# citizen_science_flora_v2_DFA_corrected.net
KiCad netlist of a schematic drawn in EAGLE
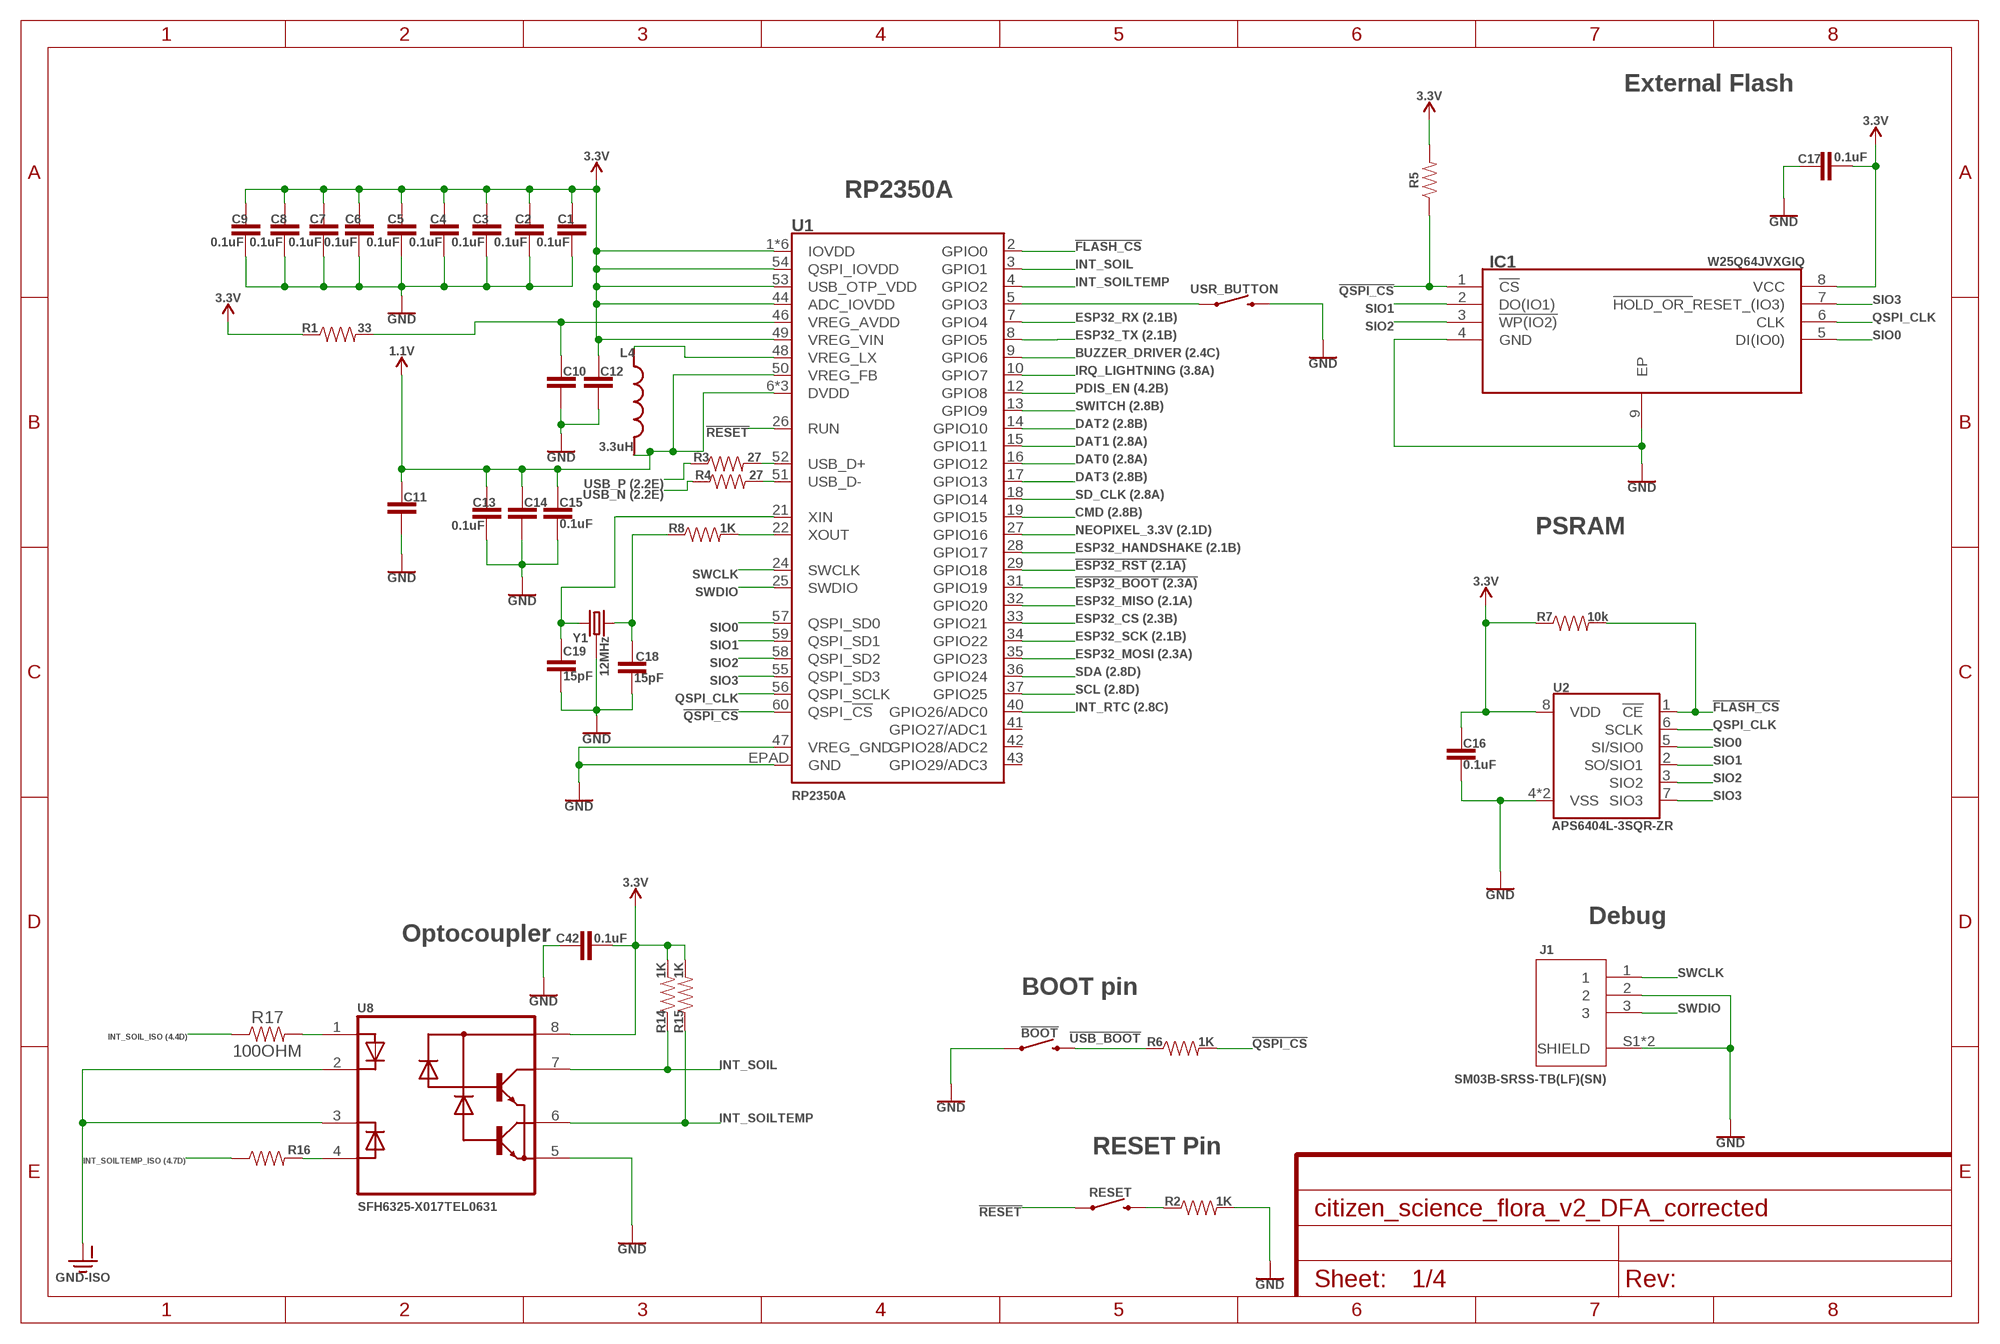
[diagram p0: schematic, sheet 1]
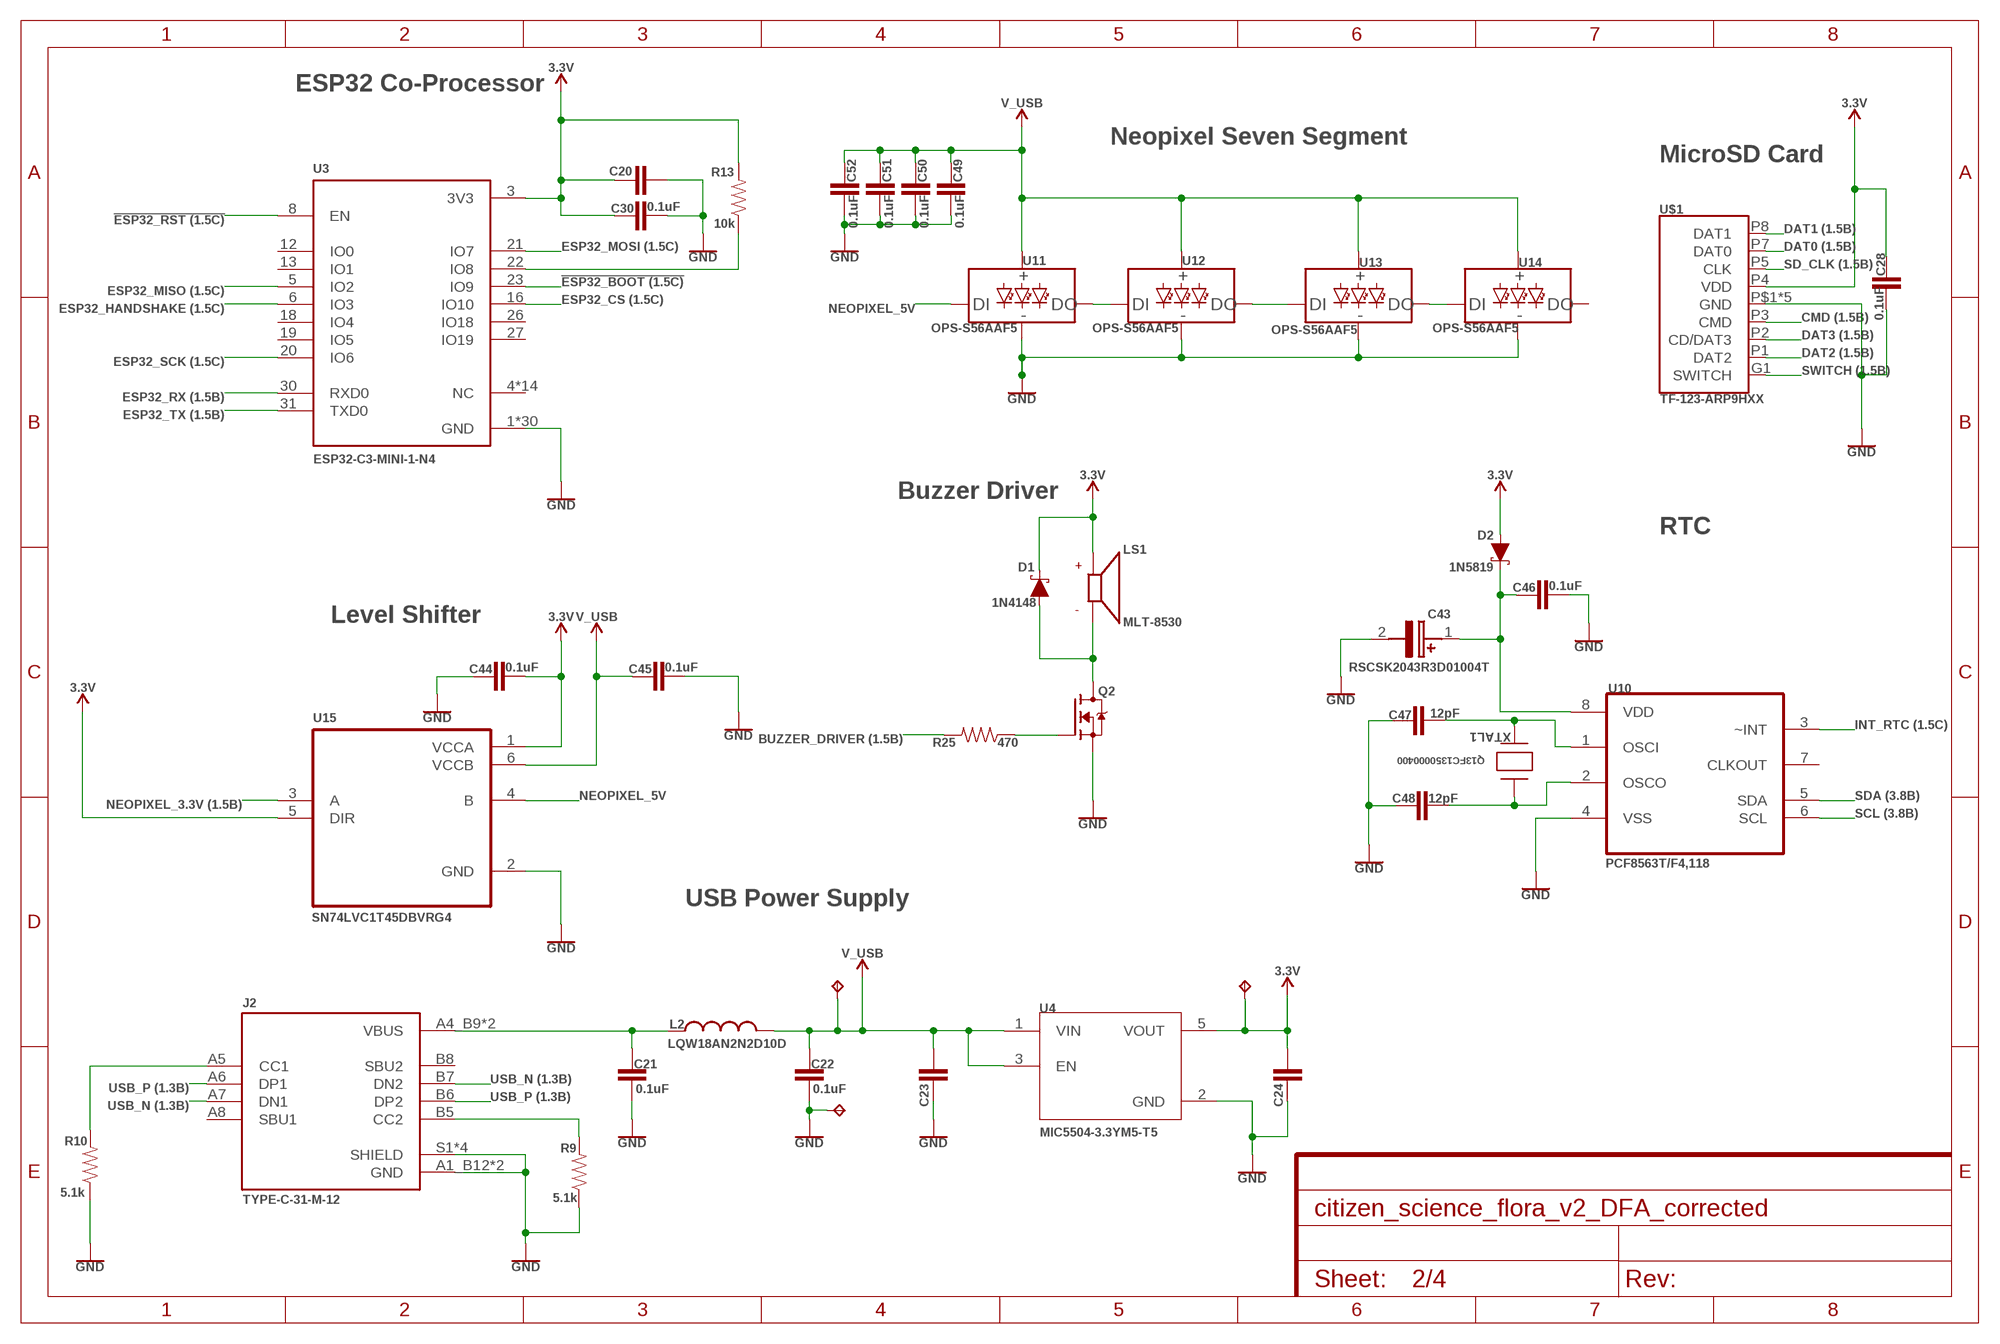
[diagram p1: schematic, sheet 2]
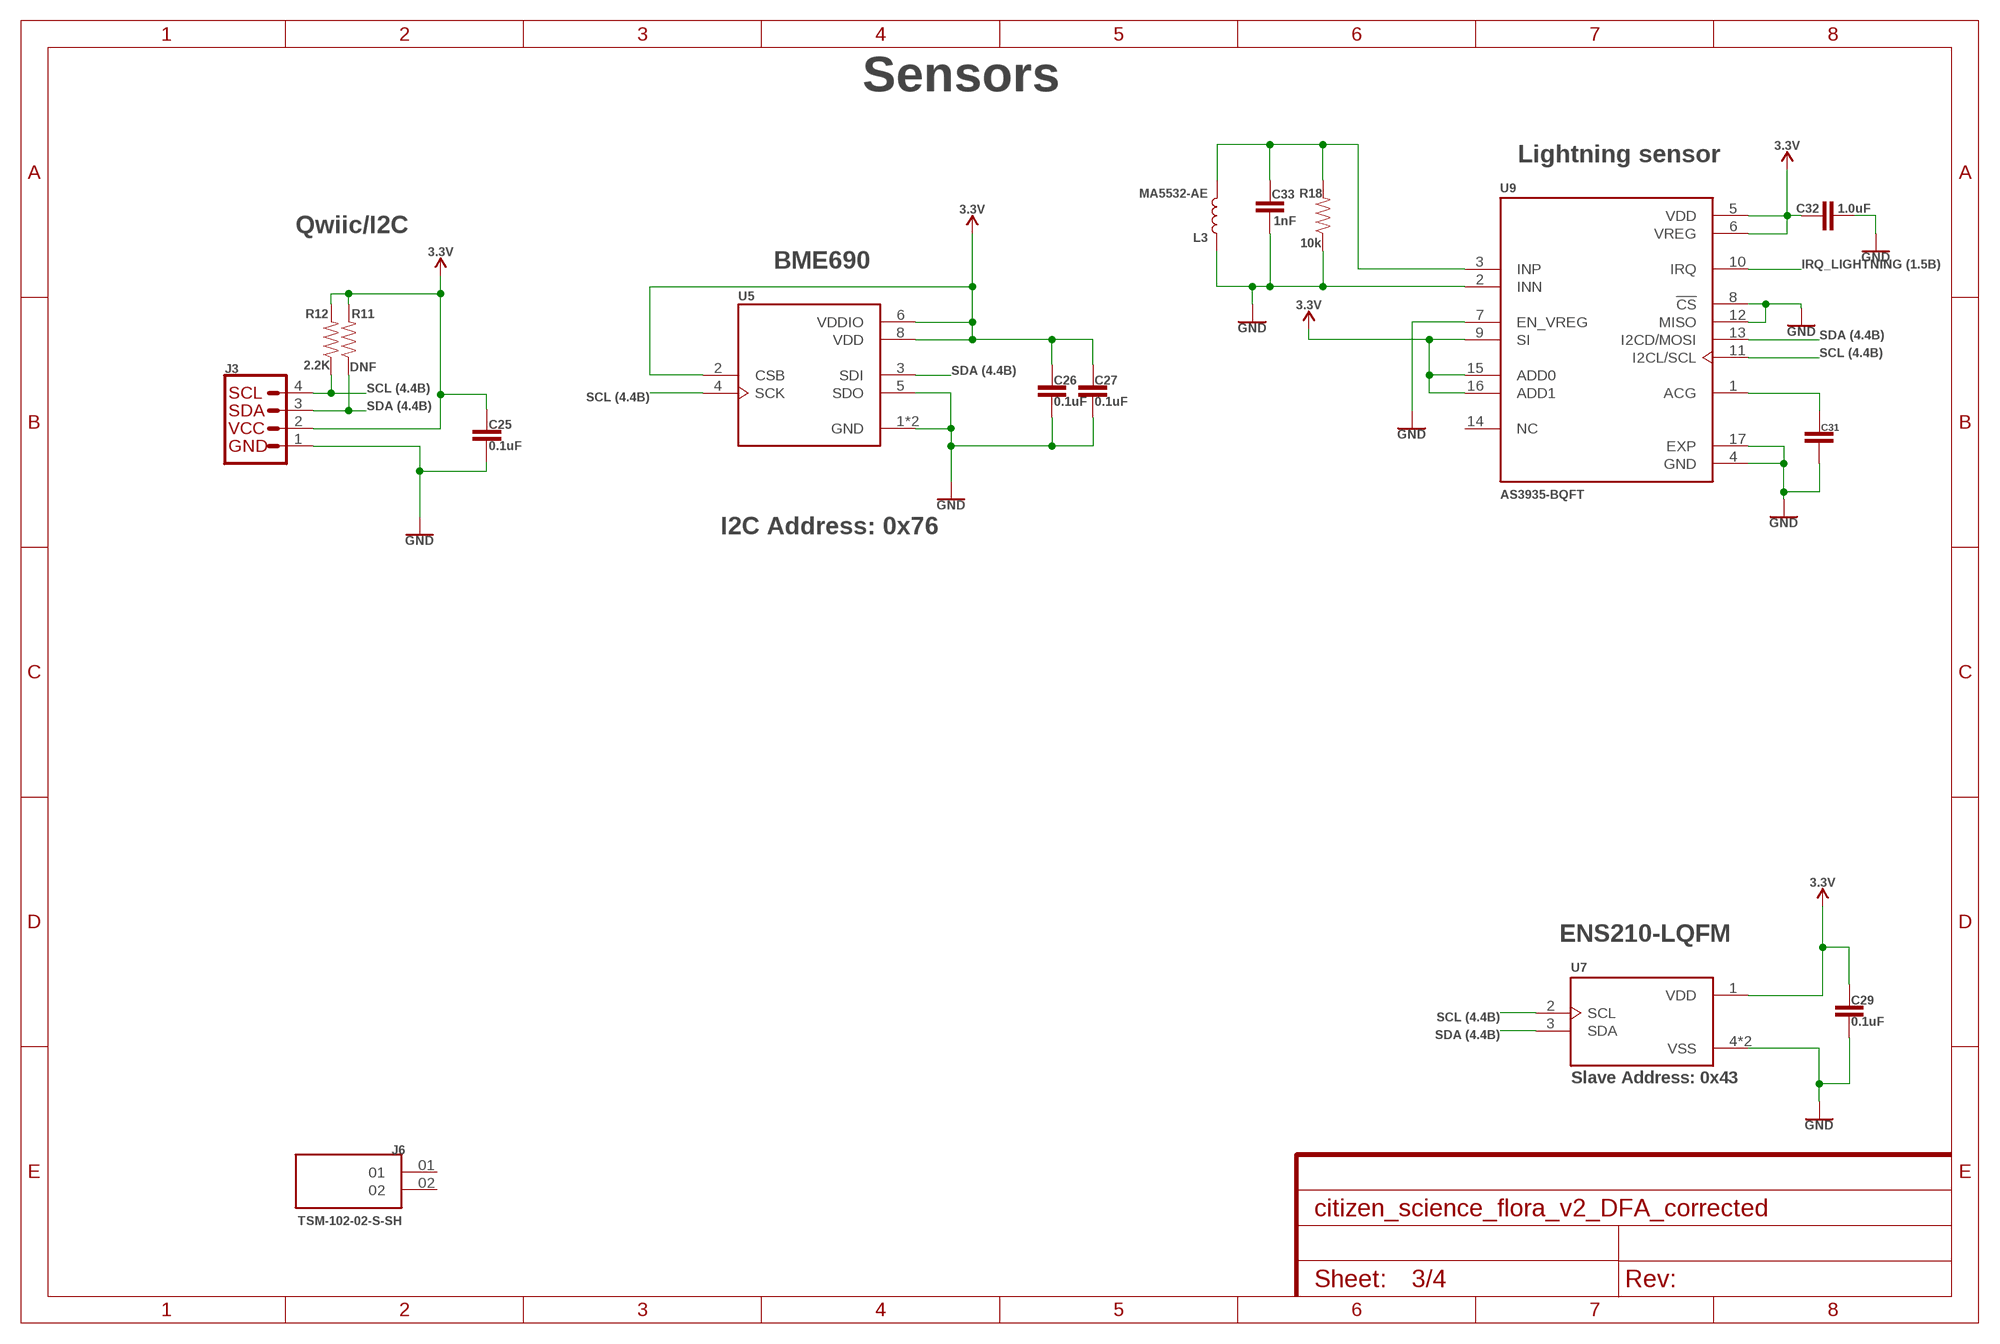
[diagram p2: schematic, sheet 3]
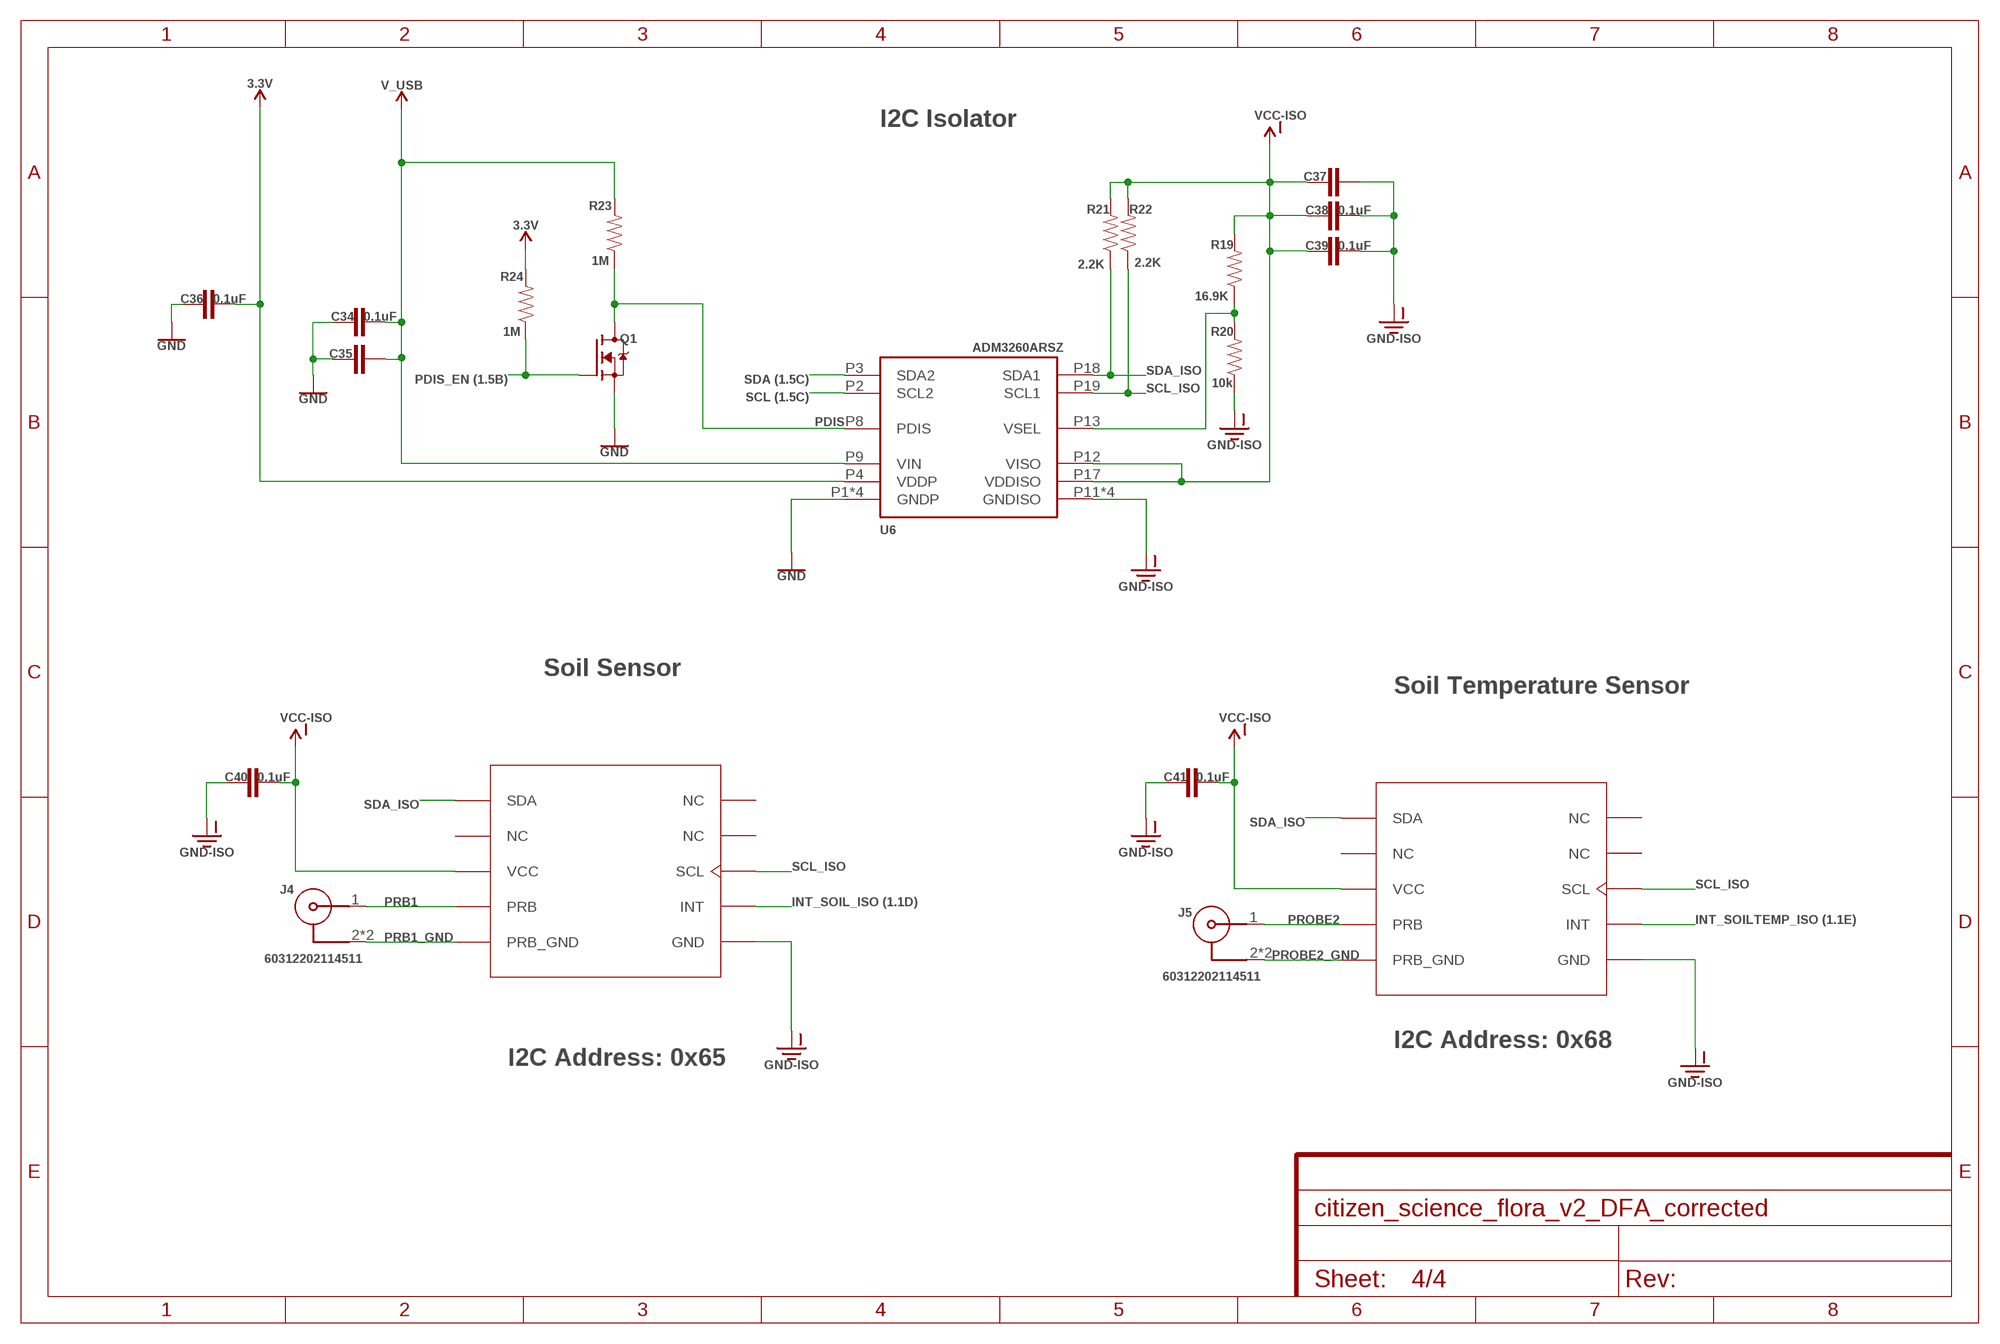
[diagram p3: schematic, sheet 4]

(export (version "E")
  (design (tool "Eeschema 10.0.6"))
  (components
    (comp (ref "C34")
      (value "0.1uF")
      (footprint "eagle-import:0402")
      (libsource (lib "eagle-import") (part "0.1UF-0402-6.3V-10%-X7R"))
    )
    (comp (ref "C35")
      (value "10UF0402")
      (footprint "eagle-import:0402")
      (libsource (lib "eagle-import") (part "10UF0402"))
    )
    (comp (ref "C36")
      (value "0.1uF")
      (footprint "eagle-import:0402")
      (libsource (lib "eagle-import") (part "0.1UF-0402-6.3V-10%-X7R"))
    )
    (comp (ref "C37")
      (value "10UF0402")
      (footprint "eagle-import:0402")
      (libsource (lib "eagle-import") (part "10UF0402"))
    )
    (comp (ref "C38")
      (value "0.1uF")
      (footprint "eagle-import:0402")
      (libsource (lib "eagle-import") (part "0.1UF-0402-6.3V-10%-X7R"))
    )
    (comp (ref "C39")
      (value "0.1uF")
      (footprint "eagle-import:0402")
      (libsource (lib "eagle-import") (part "0.1UF-0402-6.3V-10%-X7R"))
    )
    (comp (ref "C40")
      (value "0.1uF")
      (footprint "eagle-import:0402")
      (libsource (lib "eagle-import") (part "0.1UF-0402-6.3V-10%-X7R"))
    )
    (comp (ref "C41")
      (value "0.1uF")
      (footprint "eagle-import:0402")
      (libsource (lib "eagle-import") (part "0.1UF-0402-6.3V-10%-X7R"))
    )
    (comp (ref "J4")
      (value "60312202114511")
      (footprint "eagle-import:60312202114511")
      (fields (field (name "MF") "Wurth Electronics"))
      (libsource (lib "eagle-import") (part "60312202114511"))
    )
    (comp (ref "J5")
      (value "60312202114511")
      (footprint "eagle-import:60312202114511")
      (fields (field (name "MF") "Wurth Electronics"))
      (libsource (lib "eagle-import") (part "60312202114511"))
    )
    (comp (ref "Q1")
      (value "BSS138")
      (footprint "eagle-import:SOT95P240X111-3N")
      (fields (field (name "MF") "onsemi"))
      (libsource (lib "eagle-import") (part "BSS138"))
    )
    (comp (ref "R19")
      (value "16.9K")
      (footprint "eagle-import:0402")
      (libsource (lib "eagle-import") (part "RESISTOR0402"))
    )
    (comp (ref "R20")
      (value "10k")
      (footprint "eagle-import:0402")
      (libsource (lib "eagle-import") (part "SparkFun-Resistors_Sai_10KOHM-0402-1/16W-1%"))
    )
    (comp (ref "R21")
      (value "2.2K")
      (footprint "eagle-import:0402")
      (libsource (lib "eagle-import") (part "2.2KOHM-0402-1/16W-1%"))
    )
    (comp (ref "R22")
      (value "2.2K")
      (footprint "eagle-import:0402")
      (libsource (lib "eagle-import") (part "2.2KOHM-0402-1/16W-1%"))
    )
    (comp (ref "R23")
      (value "1M")
      (footprint "eagle-import:0402")
      (libsource (lib "eagle-import") (part "1MOHM-0402-1/16W-5%"))
    )
    (comp (ref "R24")
      (value "1M")
      (footprint "eagle-import:0402")
      (libsource (lib "eagle-import") (part "1MOHM-0402-1/16W-5%"))
    )
    (comp (ref "U$2")
      (value "PH-OEM")
      (footprint "eagle-import:PH_SENSOR")
      (libsource (lib "eagle-import") (part "PH-OEM"))
    )
    (comp (ref "U$3")
      (value "PH-OEM")
      (footprint "eagle-import:PH_SENSOR")
      (libsource (lib "eagle-import") (part "PH-OEM"))
    )
    (comp (ref "U6")
      (value "ADM3260ARSZ")
      (footprint "eagle-import:SSOP20")
      (fields (field (name "MF") "Analog Devices"))
      (libsource (lib "eagle-import") (part "ADM3260ARSZ"))
    )
    (comp (ref "!BOOT")
      (value "MOMENTARY-SWITCH-SPST-SMD-4.6X2.8MM")
      (footprint "eagle-import:TACTILE_SWITCH_SMD_4.6X2.8MM")
      (libsource (lib "eagle-import") (part "MOMENTARY-SWITCH-SPST-SMD-4.6X2.8MM"))
    )
    (comp (ref "C1")
      (value "0.1uF")
      (footprint "eagle-import:0402")
      (libsource (lib "eagle-import") (part "0.1UF-0402-6.3V-10%-X7R"))
    )
    (comp (ref "C2")
      (value "0.1uF")
      (footprint "eagle-import:0402")
      (libsource (lib "eagle-import") (part "0.1UF-0402-6.3V-10%-X7R"))
    )
    (comp (ref "C3")
      (value "0.1uF")
      (footprint "eagle-import:0402")
      (libsource (lib "eagle-import") (part "0.1UF-0402-6.3V-10%-X7R"))
    )
    (comp (ref "C4")
      (value "0.1uF")
      (footprint "eagle-import:0402")
      (libsource (lib "eagle-import") (part "0.1UF-0402-6.3V-10%-X7R"))
    )
    (comp (ref "C5")
      (value "0.1uF")
      (footprint "eagle-import:0402")
      (libsource (lib "eagle-import") (part "0.1UF-0402-6.3V-10%-X7R"))
    )
    (comp (ref "C6")
      (value "0.1uF")
      (footprint "eagle-import:0402")
      (libsource (lib "eagle-import") (part "0.1UF-0402-6.3V-10%-X7R"))
    )
    (comp (ref "C7")
      (value "0.1uF")
      (footprint "eagle-import:0402")
      (libsource (lib "eagle-import") (part "0.1UF-0402-6.3V-10%-X7R"))
    )
    (comp (ref "C8")
      (value "0.1uF")
      (footprint "eagle-import:0402")
      (libsource (lib "eagle-import") (part "0.1UF-0402-6.3V-10%-X7R"))
    )
    (comp (ref "C9")
      (value "0.1uF")
      (footprint "eagle-import:0402")
      (libsource (lib "eagle-import") (part "0.1UF-0402-6.3V-10%-X7R"))
    )
    (comp (ref "C10")
      (value "4.7UF0402")
      (footprint "eagle-import:0402")
      (libsource (lib "eagle-import") (part "4.7UF0402"))
    )
    (comp (ref "C11")
      (value "4.7UF0402")
      (footprint "eagle-import:0402")
      (libsource (lib "eagle-import") (part "4.7UF0402"))
    )
    (comp (ref "C12")
      (value "4.7UF0402")
      (footprint "eagle-import:0402")
      (libsource (lib "eagle-import") (part "4.7UF0402"))
    )
    (comp (ref "C13")
      (value "0.1uF")
      (footprint "eagle-import:0402")
      (libsource (lib "eagle-import") (part "0.1UF-0402-6.3V-10%-X7R"))
    )
    (comp (ref "C14")
      (value "4.7UF0402")
      (footprint "eagle-import:0402")
      (libsource (lib "eagle-import") (part "4.7UF0402"))
    )
    (comp (ref "C15")
      (value "0.1uF")
      (footprint "eagle-import:0402")
      (libsource (lib "eagle-import") (part "0.1UF-0402-6.3V-10%-X7R"))
    )
    (comp (ref "C16")
      (value "0.1uF")
      (footprint "eagle-import:0402")
      (libsource (lib "eagle-import") (part "0.1UF-0402-6.3V-10%-X7R"))
    )
    (comp (ref "C17")
      (value "0.1uF")
      (footprint "eagle-import:0402")
      (libsource (lib "eagle-import") (part "0.1UF-0402-6.3V-10%-X7R"))
    )
    (comp (ref "C18")
      (value "15pF")
      (footprint "eagle-import:0402")
      (libsource (lib "eagle-import") (part "15PF-0402-50V-5%"))
    )
    (comp (ref "C19")
      (value "15pF")
      (footprint "eagle-import:0402")
      (libsource (lib "eagle-import") (part "15PF-0402-50V-5%"))
    )
    (comp (ref "C42")
      (value "0.1uF")
      (footprint "eagle-import:0402")
      (libsource (lib "eagle-import") (part "0.1UF-0402-6.3V-10%-X7R"))
    )
    (comp (ref "IC1")
      (value "W25Q64JVXGIQ")
      (footprint "eagle-import:SON80P400X400X50-9N")
      (libsource (lib "eagle-import") (part "W25Q64JVXGIQ"))
    )
    (comp (ref "J1")
      (value "SM03B-SRSS-TB(LF)(SN)")
      (footprint "eagle-import:JST_SM03B-SRSS-TB(LF)(SN)")
      (fields (field (name "MF") "JST Sales America Inc."))
      (libsource (lib "eagle-import") (part "SM03B-SRSS-TB(LF)(SN)"))
    )
    (comp (ref "L4")
      (value "3.3uH")
      (footprint "eagle-import:IND_LQH2MCN120K02L")
      (fields (field (name "MF") "Murata") (field (name "MP") "LQH2MCN120K02L"))
      (libsource (lib "eagle-import") (part "LQH2MCN120K02L"))
    )
    (comp (ref "R1")
      (value "33")
      (footprint "eagle-import:0402")
      (libsource (lib "eagle-import") (part "33OHM-0402-1/10W-1%"))
    )
    (comp (ref "R2")
      (value "1K")
      (footprint "eagle-import:0402")
      (libsource (lib "eagle-import") (part "1KOHM-0402-1/16W-1%"))
    )
    (comp (ref "R3")
      (value "27")
      (footprint "eagle-import:0402")
      (libsource (lib "eagle-import") (part "27OHM0402"))
    )
    (comp (ref "R4")
      (value "27")
      (footprint "eagle-import:0402")
      (libsource (lib "eagle-import") (part "27OHM0402"))
    )
    (comp (ref "R5")
      (value "RESISTOR0402")
      (footprint "eagle-import:0402")
      (libsource (lib "eagle-import") (part "RESISTOR0402"))
    )
    (comp (ref "R6")
      (value "1K")
      (footprint "eagle-import:0402")
      (libsource (lib "eagle-import") (part "1KOHM-0402-1/16W-1%"))
    )
    (comp (ref "R7")
      (value "10k")
      (footprint "eagle-import:0402")
      (libsource (lib "eagle-import") (part "10KOHM-0402-1/16W-1%"))
    )
    (comp (ref "R8")
      (value "1K")
      (footprint "eagle-import:0402")
      (libsource (lib "eagle-import") (part "1KOHM-0402-1/16W-1%"))
    )
    (comp (ref "R14")
      (value "1K")
      (footprint "eagle-import:0402")
      (libsource (lib "eagle-import") (part "1KOHM-0402-1/16W-1%"))
    )
    (comp (ref "R15")
      (value "1K")
      (footprint "eagle-import:0402")
      (libsource (lib "eagle-import") (part "1KOHM-0402-1/16W-1%"))
    )
    (comp (ref "R16")
      (value "100OHM")
      (footprint "eagle-import:0402")
      (libsource (lib "eagle-import") (part "100OHM"))
    )
    (comp (ref "R17")
      (value "100OHM")
      (footprint "eagle-import:0402")
      (libsource (lib "eagle-import") (part "100OHM"))
    )
    (comp (ref "RESET")
      (value "MOMENTARY-SWITCH-SPST-SMD-4.6X2.8MM")
      (footprint "eagle-import:TACTILE_SWITCH_SMD_4.6X2.8MM")
      (libsource (lib "eagle-import") (part "MOMENTARY-SWITCH-SPST-SMD-4.6X2.8MM"))
    )
    (comp (ref "U1")
      (value "RP2350A")
      (footprint "eagle-import:RP2350A")
      (libsource (lib "eagle-import") (part "RP2350A"))
    )
    (comp (ref "U2")
      (value "APS6404L-3SQR-ZR")
      (footprint "eagle-import:APS6404L-3SQR-ZR")
      (libsource (lib "eagle-import") (part "APS6404L-3SQR-ZR"))
    )
    (comp (ref "U8")
      (value "SFH6325-X017TEL0631")
      (footprint "eagle-import:SOIC127P599X175-8N")
      (libsource (lib "eagle-import") (part "SFH6325-X017TEL0631"))
    )
    (comp (ref "USR_BUTTON")
      (value "MOMENTARY-SWITCH-SPST-SMD-4.6X2.8MM")
      (footprint "eagle-import:TACTILE_SWITCH_SMD_4.6X2.8MM")
      (libsource (lib "eagle-import") (part "MOMENTARY-SWITCH-SPST-SMD-4.6X2.8MM"))
    )
    (comp (ref "Y1")
      (value "12MHz")
      (footprint "eagle-import:CRYSTAL-SMD-3.2X2.5MM")
      (libsource (lib "eagle-import") (part "CRYSTAL-GROUNDEDSMD-3.2X2.5"))
    )
    (comp (ref "3.3V")
      (value "TPB1,27")
      (footprint "eagle-import:B1,27")
      (libsource (lib "eagle-import") (part "TPB1,27"))
    )
    (comp (ref "C20")
      (value "10UF0402")
      (footprint "eagle-import:0402")
      (libsource (lib "eagle-import") (part "10UF0402"))
    )
    (comp (ref "C21")
      (value "0.1uF")
      (footprint "eagle-import:0402")
      (libsource (lib "eagle-import") (part "0.1UF-0402-6.3V-10%-X7R"))
    )
    (comp (ref "C22")
      (value "0.1uF")
      (footprint "eagle-import:0402")
      (libsource (lib "eagle-import") (part "0.1UF-0402-6.3V-10%-X7R"))
    )
    (comp (ref "C23")
      (value "10UF0402")
      (footprint "eagle-import:0402")
      (libsource (lib "eagle-import") (part "10UF0402"))
    )
    (comp (ref "C24")
      (value "10UF0402")
      (footprint "eagle-import:0402")
      (libsource (lib "eagle-import") (part "10UF0402"))
    )
    (comp (ref "C28")
      (value "0.1uF")
      (footprint "eagle-import:0402")
      (libsource (lib "eagle-import") (part "0.1UF-0402-6.3V-10%-X7R"))
    )
    (comp (ref "C30")
      (value "0.1uF")
      (footprint "eagle-import:0402")
      (libsource (lib "eagle-import") (part "0.1UF-0402-6.3V-10%-X7R"))
    )
    (comp (ref "C43")
      (value "RSCSK2043R3D01004T")
      (footprint "eagle-import:RSCSK2043R3D01004T")
      (fields (field (name "MOUSER_PART_NUMBER") "555-DSK3R3H204T614H2"))
      (libsource (lib "eagle-import") (part "RSCSK2043R3D01004T"))
    )
    (comp (ref "C44")
      (value "0.1uF")
      (footprint "eagle-import:0402")
      (libsource (lib "eagle-import") (part "0.1UF-0402-6.3V-10%-X7R"))
    )
    (comp (ref "C45")
      (value "0.1uF")
      (footprint "eagle-import:0402")
      (libsource (lib "eagle-import") (part "0.1UF-0402-6.3V-10%-X7R"))
    )
    (comp (ref "C46")
      (value "0.1uF")
      (footprint "eagle-import:0402")
      (libsource (lib "eagle-import") (part "0.1UF-0402-6.3V-10%-X7R"))
    )
    (comp (ref "C47")
      (value "12pF")
      (footprint "eagle-import:0402")
      (libsource (lib "eagle-import") (part "12PF-0402-50V-5%"))
    )
    (comp (ref "C48")
      (value "12pF")
      (footprint "eagle-import:0402")
      (libsource (lib "eagle-import") (part "12PF-0402-50V-5%"))
    )
    (comp (ref "C49")
      (value "0.1uF")
      (footprint "eagle-import:0402")
      (libsource (lib "eagle-import") (part "0.1UF-0402-6.3V-10%-X7R"))
    )
    (comp (ref "C50")
      (value "0.1uF")
      (footprint "eagle-import:0402")
      (libsource (lib "eagle-import") (part "0.1UF-0402-6.3V-10%-X7R"))
    )
    (comp (ref "C51")
      (value "0.1uF")
      (footprint "eagle-import:0402")
      (libsource (lib "eagle-import") (part "0.1UF-0402-6.3V-10%-X7R"))
    )
    (comp (ref "C52")
      (value "0.1uF")
      (footprint "eagle-import:0402")
      (libsource (lib "eagle-import") (part "0.1UF-0402-6.3V-10%-X7R"))
    )
    (comp (ref "D1")
      (value "1N4148")
      (footprint "eagle-import:SOD-323")
      (libsource (lib "eagle-import") (part "DIODE-SCHOTTKY-BAT60A"))
    )
    (comp (ref "D2")
      (value "1N5819")
      (footprint "eagle-import:SOD-323")
      (libsource (lib "eagle-import") (part "DIODE-SCHOTTKY-BAT20J"))
    )
    (comp (ref "GND")
      (value "TPB1,27")
      (footprint "eagle-import:B1,27")
      (libsource (lib "eagle-import") (part "TPB1,27"))
    )
    (comp (ref "J2")
      (value "TYPE-C-31-M-12")
      (footprint "eagle-import:HRO_TYPE-C-31-M-12")
      (fields (field (name "MF") "HRO Electronics Co., Ltd."))
      (libsource (lib "eagle-import") (part "TYPE-C-31-M-12"))
    )
    (comp (ref "L2")
      (value "LQW18AN2N2D10D")
      (footprint "eagle-import:INDC1608X100N")
      (fields (field (name "MF") "Murata"))
      (libsource (lib "eagle-import") (part "LQW18AN2N2D10D"))
    )
    (comp (ref "LS1")
      (value "MLT-8530")
      (footprint "eagle-import:XDCR_CMT-8504-100-SMT-TR")
      (fields (field (name "MANUFACTURER") "CUI Inc."))
      (libsource (lib "eagle-import") (part "CMT-8504-100-SMT-TR"))
    )
    (comp (ref "Q2")
      (value "BSS138")
      (footprint "eagle-import:SOT95P240X111-3N")
      (fields (field (name "MF") "onsemi"))
      (libsource (lib "eagle-import") (part "BSS138"))
    )
    (comp (ref "R9")
      (value "5.1k")
      (footprint "eagle-import:0402")
      (libsource (lib "eagle-import") (part "5.1KOHM-0402-1/16W-1%"))
    )
    (comp (ref "R10")
      (value "5.1k")
      (footprint "eagle-import:0402")
      (libsource (lib "eagle-import") (part "5.1KOHM-0402-1/16W-1%"))
    )
    (comp (ref "R13")
      (value "10k")
      (footprint "eagle-import:0402")
      (libsource (lib "eagle-import") (part "10KOHM-0402-1/16W-1%"))
    )
    (comp (ref "R25")
      (value "470")
      (footprint "eagle-import:0402")
      (libsource (lib "eagle-import") (part "10KOHM-0402-1/16W-1%"))
    )
    (comp (ref "U$1")
      (value "TF-123-ARP9HXX")
      (footprint "eagle-import:MICROSDCARD")
      (libsource (lib "eagle-import") (part "TF-123-ARP9HXX"))
    )
    (comp (ref "U3")
      (value "ESP32-C3-MINI-1-N4")
      (footprint "eagle-import:XCVR_ESP32-C3-MINI-1-N4")
      (fields (field (name "MF") "Espressif Systems"))
      (libsource (lib "eagle-import") (part "ESP32-C3-MINI-1-N4"))
    )
    (comp (ref "U4")
      (value "MIC5504-3.3YM5-T5")
      (footprint "eagle-import:SOT95P280X145-5N")
      (fields (field (name "MF") "Microchip"))
      (libsource (lib "eagle-import") (part "MIC5504-3.3YM5-T5"))
    )
    (comp (ref "U10")
      (value "PCF8563T/F4,118")
      (footprint "eagle-import:SOIC127P600X175-8N")
      (fields (field (name "MF") "NXP USA"))
      (libsource (lib "eagle-import") (part "PCF8563T/F4,118"))
    )
    (comp (ref "U11")
      (value "OPS-S56AAF5")
      (footprint "eagle-import:OPS-S56AAF5")
      (libsource (lib "eagle-import") (part "OPS-S56AAF5"))
    )
    (comp (ref "U12")
      (value "OPS-S56AAF5")
      (footprint "eagle-import:OPS-S56AAF5")
      (libsource (lib "eagle-import") (part "OPS-S56AAF5"))
    )
    (comp (ref "U13")
      (value "OPS-S56AAF5")
      (footprint "eagle-import:OPS-S56AAF5")
      (libsource (lib "eagle-import") (part "OPS-S56AAF5"))
    )
    (comp (ref "U14")
      (value "OPS-S56AAF5")
      (footprint "eagle-import:OPS-S56AAF5")
      (libsource (lib "eagle-import") (part "OPS-S56AAF5"))
    )
    (comp (ref "U15")
      (value "SN74LVC1T45DBVRG4")
      (footprint "eagle-import:SOT95P280X145-6N")
      (fields (field (name "MF") "Texas Instruments"))
      (libsource (lib "eagle-import") (part "SN74LVC1T45DBVRG4"))
    )
    (comp (ref "USB")
      (value "V_USB")
      (footprint "eagle-import:B1,27")
      (libsource (lib "eagle-import") (part "TPB1,27"))
    )
    (comp (ref "XTAL1")
      (value "Q13FC1350000400")
      (footprint "eagle-import:XTAL_FC-135_EPS")
      (fields (field (name "MF") "EPSON"))
      (libsource (lib "eagle-import") (part "Q13FC1350000400"))
    )
    (comp (ref "C25")
      (value "0.1uF")
      (footprint "eagle-import:0402")
      (libsource (lib "eagle-import") (part "0.1UF-0402-6.3V-10%-X7R"))
    )
    (comp (ref "C26")
      (value "0.1uF")
      (footprint "eagle-import:0402")
      (libsource (lib "eagle-import") (part "0.1UF-0402-6.3V-10%-X7R"))
    )
    (comp (ref "C27")
      (value "0.1uF")
      (footprint "eagle-import:0402")
      (libsource (lib "eagle-import") (part "0.1UF-0402-6.3V-10%-X7R"))
    )
    (comp (ref "C29")
      (value "0.1uF")
      (footprint "eagle-import:0402")
      (libsource (lib "eagle-import") (part "0.1UF-0402-6.3V-10%-X7R"))
    )
    (comp (ref "C31")
      (value "10UF0402")
      (footprint "eagle-import:0402")
      (libsource (lib "eagle-import") (part "10UF0402"))
    )
    (comp (ref "C32")
      (value "1.0uF")
      (footprint "eagle-import:0402")
      (libsource (lib "eagle-import") (part "1.0UF-0402-16V-10%"))
    )
    (comp (ref "C33")
      (value "1nF")
      (footprint "eagle-import:0402")
      (libsource (lib "eagle-import") (part "1.0NF/1000PF-0402-25V-10%-X7R"))
    )
    (comp (ref "J3")
      (value "QWIIC_CONNECTORJS-1MM")
      (footprint "eagle-import:1X04_1MM_RA")
      (libsource (lib "eagle-import") (part "QWIIC_CONNECTORJS-1MM"))
    )
    (comp (ref "J6")
      (value "TSM-102-02-S-SH")
      (footprint "eagle-import:SAMTEC_TSM-102-02-S-SH")
      (fields (field (name "MF") "Samtec"))
      (libsource (lib "eagle-import") (part "TSM-102-02-S-SH"))
    )
    (comp (ref "L3")
      (value "MA5532-AE")
      (footprint "eagle-import:MA5532-AE")
      (fields (field (name "MF") "Coilcraft"))
      (libsource (lib "eagle-import") (part "MA5532-AE"))
    )
    (comp (ref "R11")
      (value "DNF")
      (footprint "eagle-import:0402")
      (libsource (lib "eagle-import") (part "2.2KOHM-0402-1/16W-1%"))
    )
    (comp (ref "R12")
      (value "2.2K")
      (footprint "eagle-import:0402")
      (libsource (lib "eagle-import") (part "2.2KOHM-0402-1/16W-1%"))
    )
    (comp (ref "R18")
      (value "10k")
      (footprint "eagle-import:0402")
      (libsource (lib "eagle-import") (part "SparkFun-Resistors_Sai_10KOHM-0402-1/16W-1%"))
    )
    (comp (ref "U5")
      (value "BME690")
      (footprint "eagle-import:IC_BME688")
      (fields (field (name "MF") "Bosch Sensortec") (field (name "MP") "BME688"))
      (libsource (lib "eagle-import") (part "BME690"))
    )
    (comp (ref "U7")
      (value "ENS210-LQFM")
      (footprint "eagle-import:XDCR_ENS210-LQFM")
      (fields (field (name "MF") "ScioSense"))
      (libsource (lib "eagle-import") (part "ENS210-LQFM"))
    )
    (comp (ref "U9")
      (value "AS3935-BQFT")
      (footprint "eagle-import:QFN65P400X400X80-17N")
      (fields (field (name "MF") "ScioSense"))
      (libsource (lib "eagle-import") (part "AS3935-BQFT"))
    )
  )
  (nets
    (net (code "1") (name "1.1V") (class "Default")
      (node (ref "C11") (pin "1") (pinfunction "1_1") (pintype "passive"))
      (node (ref "C13") (pin "1") (pinfunction "1_1") (pintype "passive"))
      (node (ref "C14") (pin "1") (pinfunction "1_1") (pintype "passive"))
      (node (ref "C15") (pin "1") (pinfunction "1_1") (pintype "passive"))
      (node (ref "L4") (pin "2") (pinfunction "P$2_2") (pintype "bidirectional"))
      (node (ref "U1") (pin "23") (pinfunction "DVDD_23") (pintype "bidirectional"))
      (node (ref "U1") (pin "39") (pinfunction "DVDD_39") (pintype "bidirectional"))
      (node (ref "U1") (pin "50") (pinfunction "VREG_FB_50") (pintype "bidirectional"))
      (node (ref "U1") (pin "6") (pinfunction "DVDD_6") (pintype "bidirectional"))
    )
    (net (code "2") (name "3.3V") (class "Default")
      (node (ref "3.3V") (pin "TP") (pinfunction "TP_TP") (pintype "input"))
      (node (ref "C1") (pin "1") (pinfunction "1_1") (pintype "passive"))
      (node (ref "C12") (pin "1") (pinfunction "1_1") (pintype "passive"))
      (node (ref "C16") (pin "1") (pinfunction "1_1") (pintype "passive"))
      (node (ref "C17") (pin "2") (pinfunction "2_2") (pintype "passive"))
      (node (ref "C2") (pin "1") (pinfunction "1_1") (pintype "passive"))
      (node (ref "C20") (pin "1") (pinfunction "1_1") (pintype "passive"))
      (node (ref "C24") (pin "2") (pinfunction "2_2") (pintype "passive"))
      (node (ref "C25") (pin "1") (pinfunction "1_1") (pintype "passive"))
      (node (ref "C26") (pin "1") (pinfunction "1_1") (pintype "passive"))
      (node (ref "C27") (pin "1") (pinfunction "1_1") (pintype "passive"))
      (node (ref "C28") (pin "1") (pinfunction "1_1") (pintype "passive"))
      (node (ref "C29") (pin "1") (pinfunction "1_1") (pintype "passive"))
      (node (ref "C3") (pin "1") (pinfunction "1_1") (pintype "passive"))
      (node (ref "C30") (pin "1") (pinfunction "1_1") (pintype "passive"))
      (node (ref "C32") (pin "1") (pinfunction "1_1") (pintype "passive"))
      (node (ref "C36") (pin "2") (pinfunction "2_2") (pintype "passive"))
      (node (ref "C4") (pin "1") (pinfunction "1_1") (pintype "passive"))
      (node (ref "C42") (pin "2") (pinfunction "2_2") (pintype "passive"))
      (node (ref "C44") (pin "2") (pinfunction "2_2") (pintype "passive"))
      (node (ref "C5") (pin "1") (pinfunction "1_1") (pintype "passive"))
      (node (ref "C6") (pin "1") (pinfunction "1_1") (pintype "passive"))
      (node (ref "C7") (pin "1") (pinfunction "1_1") (pintype "passive"))
      (node (ref "C8") (pin "1") (pinfunction "1_1") (pintype "passive"))
      (node (ref "C9") (pin "1") (pinfunction "1_1") (pintype "passive"))
      (node (ref "D1") (pin "C") (pinfunction "C_C") (pintype "passive"))
      (node (ref "D2") (pin "A") (pinfunction "A_A") (pintype "passive"))
      (node (ref "IC1") (pin "8") (pinfunction "VCC_8") (pintype "bidirectional"))
      (node (ref "J3") (pin "2") (pinfunction "2_2") (pintype "power_in"))
      (node (ref "LS1") (pin "P") (pinfunction "P_P") (pintype "passive"))
      (node (ref "R1") (pin "1") (pinfunction "1_1") (pintype "passive"))
      (node (ref "R11") (pin "2") (pinfunction "2_2") (pintype "passive"))
      (node (ref "R12") (pin "2") (pinfunction "2_2") (pintype "passive"))
      (node (ref "R13") (pin "2") (pinfunction "2_2") (pintype "passive"))
      (node (ref "R14") (pin "2") (pinfunction "2_2") (pintype "passive"))
      (node (ref "R15") (pin "2") (pinfunction "2_2") (pintype "passive"))
      (node (ref "R24") (pin "2") (pinfunction "2_2") (pintype "passive"))
      (node (ref "R5") (pin "2") (pinfunction "2_2") (pintype "passive"))
      (node (ref "R7") (pin "1") (pinfunction "1_1") (pintype "passive"))
      (node (ref "U$1") (pin "P4") (pinfunction "VDD_P4") (pintype "power_in"))
      (node (ref "U1") (pin "1") (pinfunction "IOVDD_1") (pintype "bidirectional"))
      (node (ref "U1") (pin "11") (pinfunction "IOVDD_11") (pintype "bidirectional"))
      (node (ref "U1") (pin "20") (pinfunction "IOVDD_20") (pintype "bidirectional"))
      (node (ref "U1") (pin "30") (pinfunction "IOVDD_30") (pintype "bidirectional"))
      (node (ref "U1") (pin "38") (pinfunction "IOVDD_38") (pintype "bidirectional"))
      (node (ref "U1") (pin "44") (pinfunction "ADC_IOVDD_44") (pintype "bidirectional"))
      (node (ref "U1") (pin "45") (pinfunction "IOVDD_45") (pintype "bidirectional"))
      (node (ref "U1") (pin "49") (pinfunction "VREG_VIN_49") (pintype "bidirectional"))
      (node (ref "U1") (pin "53") (pinfunction "USB_OTP_VDD_53") (pintype "bidirectional"))
      (node (ref "U1") (pin "54") (pinfunction "QSPI_IOVDD_54") (pintype "bidirectional"))
      (node (ref "U15") (pin "1") (pinfunction "VCCA_1") (pintype "power_in"))
      (node (ref "U15") (pin "5") (pinfunction "DIR_5") (pintype "input"))
      (node (ref "U2") (pin "8") (pinfunction "VDD_8") (pintype "bidirectional"))
      (node (ref "U3") (pin "3") (pinfunction "3V3_3") (pintype "power_in"))
      (node (ref "U4") (pin "5") (pinfunction "VOUT_5") (pintype "output"))
      (node (ref "U5") (pin "2") (pinfunction "CSB_2") (pintype "input"))
      (node (ref "U5") (pin "6") (pinfunction "VDDIO_6") (pintype "power_in"))
      (node (ref "U5") (pin "8") (pinfunction "VDD_8") (pintype "power_in"))
      (node (ref "U6") (pin "P4") (pinfunction "VDDP_P4") (pintype "bidirectional"))
      (node (ref "U7") (pin "1") (pinfunction "VDD_1") (pintype "power_in"))
      (node (ref "U8") (pin "8") (pinfunction "C(VCC)_8") (pintype "passive"))
      (node (ref "U9") (pin "15") (pinfunction "ADD0_15") (pintype "input"))
      (node (ref "U9") (pin "16") (pinfunction "ADD1_16") (pintype "input"))
      (node (ref "U9") (pin "5") (pinfunction "VDD_5") (pintype "power_in"))
      (node (ref "U9") (pin "6") (pinfunction "VREG_6") (pintype "power_in"))
      (node (ref "U9") (pin "9") (pinfunction "SI_9") (pintype "input"))
    )
    (net (code "3") (name "BUZZER_DRIVER") (class "Default")
      (node (ref "R25") (pin "2") (pinfunction "2_2") (pintype "passive"))
      (node (ref "U1") (pin "9") (pinfunction "GPIO6_9") (pintype "bidirectional"))
    )
    (net (code "4") (name "CMD") (class "Default")
      (node (ref "U$1") (pin "P3") (pinfunction "CMD_P3") (pintype "bidirectional"))
      (node (ref "U1") (pin "19") (pinfunction "GPIO15_19") (pintype "bidirectional"))
    )
    (net (code "5") (name "DAT0") (class "Default")
      (node (ref "U$1") (pin "P7") (pinfunction "DAT0_P7") (pintype "bidirectional"))
      (node (ref "U1") (pin "16") (pinfunction "GPIO12_16") (pintype "bidirectional"))
    )
    (net (code "6") (name "DAT1") (class "Default")
      (node (ref "U$1") (pin "P8") (pinfunction "DAT1_P8") (pintype "bidirectional"))
      (node (ref "U1") (pin "15") (pinfunction "GPIO11_15") (pintype "bidirectional"))
    )
    (net (code "7") (name "DAT2") (class "Default")
      (node (ref "U$1") (pin "P1") (pinfunction "DAT2_P1") (pintype "bidirectional"))
      (node (ref "U1") (pin "14") (pinfunction "GPIO10_14") (pintype "bidirectional"))
    )
    (net (code "8") (name "DAT3") (class "Default")
      (node (ref "U$1") (pin "P2") (pinfunction "CD/DAT3_P2") (pintype "bidirectional"))
      (node (ref "U1") (pin "17") (pinfunction "GPIO13_17") (pintype "bidirectional"))
    )
    (net (code "9") (name "ESP32_CS") (class "Default")
      (node (ref "U1") (pin "33") (pinfunction "GPIO21_33") (pintype "bidirectional"))
      (node (ref "U3") (pin "16") (pinfunction "IO10_16") (pintype "bidirectional"))
    )
    (net (code "10") (name "ESP32_HANDSHAKE") (class "Default")
      (node (ref "U1") (pin "28") (pinfunction "GPIO17_28") (pintype "bidirectional"))
      (node (ref "U3") (pin "6") (pinfunction "IO3_6") (pintype "bidirectional"))
    )
    (net (code "11") (name "ESP32_MISO") (class "Default")
      (node (ref "U1") (pin "32") (pinfunction "GPIO20_32") (pintype "bidirectional"))
      (node (ref "U3") (pin "5") (pinfunction "IO2_5") (pintype "bidirectional"))
    )
    (net (code "12") (name "ESP32_MOSI") (class "Default")
      (node (ref "U1") (pin "35") (pinfunction "GPIO23_35") (pintype "bidirectional"))
      (node (ref "U3") (pin "21") (pinfunction "IO7_21") (pintype "bidirectional"))
    )
    (net (code "13") (name "ESP32_RX") (class "Default")
      (node (ref "U1") (pin "7") (pinfunction "GPIO4_7") (pintype "bidirectional"))
      (node (ref "U3") (pin "30") (pinfunction "RXD0_30") (pintype "bidirectional"))
    )
    (net (code "14") (name "ESP32_SCK") (class "Default")
      (node (ref "U1") (pin "34") (pinfunction "GPIO22_34") (pintype "bidirectional"))
      (node (ref "U3") (pin "20") (pinfunction "IO6_20") (pintype "bidirectional"))
    )
    (net (code "15") (name "ESP32_TX") (class "Default")
      (node (ref "U1") (pin "8") (pinfunction "GPIO5_8") (pintype "bidirectional"))
      (node (ref "U3") (pin "31") (pinfunction "TXD0_31") (pintype "bidirectional"))
    )
    (net (code "16") (name "GND") (class "Default")
      (node (ref "!BOOT") (pin "1") (pinfunction "1_1") (pintype "passive"))
      (node (ref "!BOOT") (pin "2") (pinfunction "1_2") (pintype "passive"))
      (node (ref "C1") (pin "2") (pinfunction "2_2") (pintype "passive"))
      (node (ref "C10") (pin "2") (pinfunction "2_2") (pintype "passive"))
      (node (ref "C11") (pin "2") (pinfunction "2_2") (pintype "passive"))
      (node (ref "C12") (pin "2") (pinfunction "2_2") (pintype "passive"))
      (node (ref "C13") (pin "2") (pinfunction "2_2") (pintype "passive"))
      (node (ref "C14") (pin "2") (pinfunction "2_2") (pintype "passive"))
      (node (ref "C15") (pin "2") (pinfunction "2_2") (pintype "passive"))
      (node (ref "C16") (pin "2") (pinfunction "2_2") (pintype "passive"))
      (node (ref "C17") (pin "1") (pinfunction "1_1") (pintype "passive"))
      (node (ref "C18") (pin "2") (pinfunction "2_2") (pintype "passive"))
      (node (ref "C19") (pin "2") (pinfunction "2_2") (pintype "passive"))
      (node (ref "C2") (pin "2") (pinfunction "2_2") (pintype "passive"))
      (node (ref "C20") (pin "2") (pinfunction "2_2") (pintype "passive"))
      (node (ref "C21") (pin "2") (pinfunction "2_2") (pintype "passive"))
      (node (ref "C22") (pin "2") (pinfunction "2_2") (pintype "passive"))
      (node (ref "C23") (pin "1") (pinfunction "1_1") (pintype "passive"))
      (node (ref "C24") (pin "1") (pinfunction "1_1") (pintype "passive"))
      (node (ref "C25") (pin "2") (pinfunction "2_2") (pintype "passive"))
      (node (ref "C26") (pin "2") (pinfunction "2_2") (pintype "passive"))
      (node (ref "C27") (pin "2") (pinfunction "2_2") (pintype "passive"))
      (node (ref "C28") (pin "2") (pinfunction "2_2") (pintype "passive"))
      (node (ref "C29") (pin "2") (pinfunction "2_2") (pintype "passive"))
      (node (ref "C3") (pin "2") (pinfunction "2_2") (pintype "passive"))
      (node (ref "C30") (pin "2") (pinfunction "2_2") (pintype "passive"))
      (node (ref "C31") (pin "2") (pinfunction "2_2") (pintype "passive"))
      (node (ref "C32") (pin "2") (pinfunction "2_2") (pintype "passive"))
      (node (ref "C33") (pin "2") (pinfunction "2_2") (pintype "passive"))
      (node (ref "C34") (pin "1") (pinfunction "1_1") (pintype "passive"))
      (node (ref "C35") (pin "1") (pinfunction "1_1") (pintype "passive"))
      (node (ref "C36") (pin "1") (pinfunction "1_1") (pintype "passive"))
      (node (ref "C4") (pin "2") (pinfunction "2_2") (pintype "passive"))
      (node (ref "C42") (pin "1") (pinfunction "1_1") (pintype "passive"))
      (node (ref "C43") (pin "2") (pinfunction "-_2") (pintype "bidirectional"))
      (node (ref "C44") (pin "1") (pinfunction "1_1") (pintype "passive"))
      (node (ref "C45") (pin "2") (pinfunction "2_2") (pintype "passive"))
      (node (ref "C46") (pin "2") (pinfunction "2_2") (pintype "passive"))
      (node (ref "C47") (pin "1") (pinfunction "1_1") (pintype "passive"))
      (node (ref "C48") (pin "1") (pinfunction "1_1") (pintype "passive"))
      (node (ref "C49") (pin "2") (pinfunction "2_2") (pintype "passive"))
      (node (ref "C5") (pin "2") (pinfunction "2_2") (pintype "passive"))
      (node (ref "C50") (pin "2") (pinfunction "2_2") (pintype "passive"))
      (node (ref "C51") (pin "2") (pinfunction "2_2") (pintype "passive"))
      (node (ref "C52") (pin "2") (pinfunction "2_2") (pintype "passive"))
      (node (ref "C6") (pin "2") (pinfunction "2_2") (pintype "passive"))
      (node (ref "C7") (pin "2") (pinfunction "2_2") (pintype "passive"))
      (node (ref "C8") (pin "2") (pinfunction "2_2") (pintype "passive"))
      (node (ref "C9") (pin "2") (pinfunction "2_2") (pintype "passive"))
      (node (ref "GND") (pin "TP") (pinfunction "TP_TP") (pintype "input"))
      (node (ref "IC1") (pin "4") (pinfunction "GND_4") (pintype "bidirectional"))
      (node (ref "IC1") (pin "9") (pinfunction "EP_9") (pintype "bidirectional"))
      (node (ref "J1") (pin "2") (pinfunction "2_2") (pintype "passive"))
      (node (ref "J1") (pin "S1") (pinfunction "SHIELD_S1") (pintype "passive"))
      (node (ref "J1") (pin "S2") (pinfunction "SHIELD_S2") (pintype "passive"))
      (node (ref "J2") (pin "A1_B12") (pinfunction "GND_A1_B12") (pintype "power_in"))
      (node (ref "J2") (pin "B1_A12") (pinfunction "GND_B1_A12") (pintype "power_in"))
      (node (ref "J2") (pin "S1") (pinfunction "SHIELD_S1") (pintype "passive"))
      (node (ref "J2") (pin "S2") (pinfunction "SHIELD_S2") (pintype "passive"))
      (node (ref "J2") (pin "S3") (pinfunction "SHIELD_S3") (pintype "passive"))
      (node (ref "J2") (pin "S4") (pinfunction "SHIELD_S4") (pintype "passive"))
      (node (ref "J3") (pin "1") (pinfunction "1_1") (pintype "power_in"))
      (node (ref "L3") (pin "1") (pinfunction "1_1") (pintype "passive"))
      (node (ref "Q1") (pin "2") (pinfunction "S_2") (pintype "passive"))
      (node (ref "Q2") (pin "2") (pinfunction "S_2") (pintype "passive"))
      (node (ref "R10") (pin "1") (pinfunction "1_1") (pintype "passive"))
      (node (ref "R18") (pin "1") (pinfunction "1_1") (pintype "passive"))
      (node (ref "R2") (pin "2") (pinfunction "2_2") (pintype "passive"))
      (node (ref "R9") (pin "1") (pinfunction "1_1") (pintype "passive"))
      (node (ref "U$1") (pin "P$1") (pinfunction "GND_P$1") (pintype "power_in"))
      (node (ref "U$1") (pin "P$2") (pinfunction "GND_P$2") (pintype "power_in"))
      (node (ref "U$1") (pin "P$3") (pinfunction "GND_P$3") (pintype "power_in"))
      (node (ref "U$1") (pin "P$4") (pinfunction "GND_P$4") (pintype "power_in"))
      (node (ref "U$1") (pin "P6") (pinfunction "GND_P6") (pintype "power_in"))
      (node (ref "U1") (pin "47") (pinfunction "VREG_GND_47") (pintype "bidirectional"))
      (node (ref "U1") (pin "EPAD") (pinfunction "GND_EPAD") (pintype "bidirectional"))
      (node (ref "U10") (pin "4") (pinfunction "VSS_4") (pintype "power_in"))
      (node (ref "U11") (pin "P$3") (pinfunction "GND_P$3") (pintype "bidirectional"))
      (node (ref "U12") (pin "P$3") (pinfunction "GND_P$3") (pintype "bidirectional"))
      (node (ref "U13") (pin "P$3") (pinfunction "GND_P$3") (pintype "bidirectional"))
      (node (ref "U14") (pin "P$3") (pinfunction "GND_P$3") (pintype "bidirectional"))
      (node (ref "U15") (pin "2") (pinfunction "GND_2") (pintype "power_in"))
      (node (ref "U2") (pin "4") (pinfunction "VSS_4") (pintype "bidirectional"))
      (node (ref "U2") (pin "9") (pinfunction "VSS_9") (pintype "bidirectional"))
      (node (ref "U3") (pin "1") (pinfunction "GND_1") (pintype "power_in"))
      (node (ref "U3") (pin "11") (pinfunction "GND_11") (pintype "power_in"))
      (node (ref "U3") (pin "14") (pinfunction "GND_14") (pintype "power_in"))
      (node (ref "U3") (pin "2") (pinfunction "GND_2") (pintype "power_in"))
      (node (ref "U3") (pin "36") (pinfunction "GND_36") (pintype "power_in"))
      (node (ref "U3") (pin "37") (pinfunction "GND_37") (pintype "power_in"))
      (node (ref "U3") (pin "38") (pinfunction "GND_38") (pintype "power_in"))
      (node (ref "U3") (pin "39") (pinfunction "GND_39") (pintype "power_in"))
      (node (ref "U3") (pin "40") (pinfunction "GND_40") (pintype "power_in"))
      (node (ref "U3") (pin "41") (pinfunction "GND_41") (pintype "power_in"))
      (node (ref "U3") (pin "42") (pinfunction "GND_42") (pintype "power_in"))
      (node (ref "U3") (pin "43") (pinfunction "GND_43") (pintype "power_in"))
      (node (ref "U3") (pin "44") (pinfunction "GND_44") (pintype "power_in"))
      (node (ref "U3") (pin "45") (pinfunction "GND_45") (pintype "power_in"))
      (node (ref "U3") (pin "46") (pinfunction "GND_46") (pintype "power_in"))
      (node (ref "U3") (pin "47") (pinfunction "GND_47") (pintype "power_in"))
      (node (ref "U3") (pin "48") (pinfunction "GND_48") (pintype "power_in"))
      (node (ref "U3") (pin "49_1") (pinfunction "GND_49_1") (pintype "power_in"))
      (node (ref "U3") (pin "49_2") (pinfunction "GND_49_2") (pintype "power_in"))
      (node (ref "U3") (pin "49_3") (pinfunction "GND_49_3") (pintype "power_in"))
      (node (ref "U3") (pin "49_4") (pinfunction "GND_49_4") (pintype "power_in"))
      (node (ref "U3") (pin "49_5") (pinfunction "GND_49_5") (pintype "power_in"))
      (node (ref "U3") (pin "49_6") (pinfunction "GND_49_6") (pintype "power_in"))
      (node (ref "U3") (pin "49_7") (pinfunction "GND_49_7") (pintype "power_in"))
      (node (ref "U3") (pin "49_8") (pinfunction "GND_49_8") (pintype "power_in"))
      (node (ref "U3") (pin "49_9") (pinfunction "GND_49_9") (pintype "power_in"))
      (node (ref "U3") (pin "50") (pinfunction "GND_50") (pintype "power_in"))
      (node (ref "U3") (pin "51") (pinfunction "GND_51") (pintype "power_in"))
      (node (ref "U3") (pin "52") (pinfunction "GND_52") (pintype "power_in"))
      (node (ref "U3") (pin "53") (pinfunction "GND_53") (pintype "power_in"))
      (node (ref "U4") (pin "2") (pinfunction "GND_2") (pintype "power_in"))
      (node (ref "U5") (pin "1") (pinfunction "GND_1") (pintype "power_in"))
      (node (ref "U5") (pin "5") (pinfunction "SDO_5") (pintype "bidirectional"))
      (node (ref "U5") (pin "7") (pinfunction "GND_7") (pintype "power_in"))
      (node (ref "U6") (pin "P1") (pinfunction "GNDP_P1") (pintype "bidirectional"))
      (node (ref "U6") (pin "P10") (pinfunction "GNDP_P10") (pintype "bidirectional"))
      (node (ref "U6") (pin "P5") (pinfunction "GNDP_P5") (pintype "bidirectional"))
      (node (ref "U6") (pin "P7") (pinfunction "GNDP_P7") (pintype "bidirectional"))
      (node (ref "U7") (pin "4") (pinfunction "VSS_4") (pintype "power_in"))
      (node (ref "U7") (pin "5") (pinfunction "VSS_5") (pintype "power_in"))
      (node (ref "U8") (pin "5") (pinfunction "E(GND)_5") (pintype "passive"))
      (node (ref "U9") (pin "12") (pinfunction "MISO_12") (pintype "output"))
      (node (ref "U9") (pin "17") (pinfunction "EXP_17") (pintype "power_in"))
      (node (ref "U9") (pin "2") (pinfunction "INN_2") (pintype "bidirectional"))
      (node (ref "U9") (pin "4") (pinfunction "GND_4") (pintype "power_in"))
      (node (ref "U9") (pin "7") (pinfunction "EN_VREG_7") (pintype "input"))
      (node (ref "U9") (pin "8") (pinfunction "~{CS}_8") (pintype "input"))
      (node (ref "USR_BUTTON") (pin "3") (pinfunction "2_3") (pintype "passive"))
      (node (ref "USR_BUTTON") (pin "4") (pinfunction "2_4") (pintype "passive"))
      (node (ref "Y1") (pin "2") (pinfunction "GND_2") (pintype "power_in"))
      (node (ref "Y1") (pin "4") (pinfunction "GND_4") (pintype "power_in"))
    )
    (net (code "17") (name "GND-ISO") (class "Default")
      (node (ref "C37") (pin "2") (pinfunction "2_2") (pintype "passive"))
      (node (ref "C38") (pin "2") (pinfunction "2_2") (pintype "passive"))
      (node (ref "C39") (pin "2") (pinfunction "2_2") (pintype "passive"))
      (node (ref "C40") (pin "1") (pinfunction "1_1") (pintype "passive"))
      (node (ref "C41") (pin "1") (pinfunction "1_1") (pintype "passive"))
      (node (ref "R20") (pin "1") (pinfunction "1_1") (pintype "passive"))
      (node (ref "U$2") (pin "P$6") (pinfunction "GND_P$6") (pintype "power_in"))
      (node (ref "U$3") (pin "P$6") (pinfunction "GND_P$6") (pintype "power_in"))
      (node (ref "U6") (pin "P11") (pinfunction "GNDISO_P11") (pintype "bidirectional"))
      (node (ref "U6") (pin "P14") (pinfunction "GNDISO_P14") (pintype "bidirectional"))
      (node (ref "U6") (pin "P16") (pinfunction "GNDISO_P16") (pintype "bidirectional"))
      (node (ref "U6") (pin "P20") (pinfunction "GNDISO_P20") (pintype "bidirectional"))
      (node (ref "U8") (pin "2") (pinfunction "C1_2") (pintype "passive"))
      (node (ref "U8") (pin "3") (pinfunction "C2_3") (pintype "passive"))
    )
    (net (code "18") (name "INT_RTC") (class "Default")
      (node (ref "U1") (pin "40") (pinfunction "GPIO26/ADC0_40") (pintype "bidirectional"))
      (node (ref "U10") (pin "3") (pinfunction "~{INT}_3") (pintype "output"))
    )
    (net (code "19") (name "INT_SOIL") (class "Default")
      (node (ref "R14") (pin "1") (pinfunction "1_1") (pintype "passive"))
      (node (ref "U1") (pin "3") (pinfunction "GPIO1_3") (pintype "bidirectional"))
      (node (ref "U8") (pin "7") (pinfunction "C1(VO1)_7") (pintype "passive"))
    )
    (net (code "20") (name "INT_SOILTEMP") (class "Default")
      (node (ref "R15") (pin "1") (pinfunction "1_1") (pintype "passive"))
      (node (ref "U1") (pin "4") (pinfunction "GPIO2_4") (pintype "bidirectional"))
      (node (ref "U8") (pin "6") (pinfunction "C2(VO2)_6") (pintype "passive"))
    )
    (net (code "21") (name "INT_SOILTEMP_ISO") (class "Default")
      (node (ref "R16") (pin "1") (pinfunction "1_1") (pintype "passive"))
      (node (ref "U$3") (pin "P$7") (pinfunction "INT_P$7") (pintype "bidirectional"))
    )
    (net (code "22") (name "INT_SOIL_ISO") (class "Default")
      (node (ref "R17") (pin "1") (pinfunction "1_1") (pintype "passive"))
      (node (ref "U$2") (pin "P$7") (pinfunction "INT_P$7") (pintype "bidirectional"))
    )
    (net (code "23") (name "IRQ_LIGHTNING") (class "Default")
      (node (ref "U1") (pin "10") (pinfunction "GPIO7_10") (pintype "bidirectional"))
      (node (ref "U9") (pin "10") (pinfunction "IRQ_10") (pintype "output"))
    )
    (net (code "24") (name "NEOPIXEL_3.3V") (class "Default")
      (node (ref "U1") (pin "27") (pinfunction "GPIO16_27") (pintype "bidirectional"))
      (node (ref "U15") (pin "3") (pinfunction "A_3") (pintype "input"))
    )
    (net (code "25") (name "NEOPIXEL_5V") (class "Default")
      (node (ref "U11") (pin "P$4") (pinfunction "DI_P$4") (pintype "bidirectional"))
      (node (ref "U15") (pin "4") (pinfunction "B_4") (pintype "output"))
    )
    (net (code "26") (name "Net-(C21-Pad1)") (class "Default")
      (node (ref "C21") (pin "1") (pinfunction "1_1") (pintype "passive"))
      (node (ref "J2") (pin "A4_B9") (pinfunction "VBUS_A4_B9") (pintype "power_in"))
      (node (ref "J2") (pin "B4_A9") (pinfunction "VBUS_B4_A9") (pintype "power_in"))
      (node (ref "L2") (pin "1") (pinfunction "1_1") (pintype "passive"))
    )
    (net (code "27") (name "Net-(C43-+)") (class "Default")
      (node (ref "C43") (pin "1") (pinfunction "+_1") (pintype "bidirectional"))
      (node (ref "C46") (pin "1") (pinfunction "1_1") (pintype "passive"))
      (node (ref "D2") (pin "C") (pinfunction "C_C") (pintype "passive"))
      (node (ref "U10") (pin "8") (pinfunction "VDD_8") (pintype "power_in"))
    )
    (net (code "28") (name "Net-(J2-CC1)") (class "Default")
      (node (ref "J2") (pin "A5") (pinfunction "CC1_A5") (pintype "bidirectional"))
      (node (ref "R10") (pin "2") (pinfunction "2_2") (pintype "passive"))
    )
    (net (code "29") (name "Net-(J2-CC2)") (class "Default")
      (node (ref "J2") (pin "B5") (pinfunction "CC2_B5") (pintype "bidirectional"))
      (node (ref "R9") (pin "2") (pinfunction "2_2") (pintype "passive"))
    )
    (net (code "30") (name "Net-(L4-P$1)") (class "Default")
      (node (ref "L4") (pin "1") (pinfunction "P$1_1") (pintype "bidirectional"))
      (node (ref "U1") (pin "48") (pinfunction "VREG_LX_48") (pintype "bidirectional"))
    )
    (net (code "31") (name "Net-(Q2-D)") (class "Default")
      (node (ref "D1") (pin "A") (pinfunction "A_A") (pintype "passive"))
      (node (ref "LS1") (pin "N") (pinfunction "N_N") (pintype "passive"))
      (node (ref "Q2") (pin "3") (pinfunction "D_3") (pintype "passive"))
    )
    (net (code "32") (name "Net-(Q2-G)") (class "Default")
      (node (ref "Q2") (pin "1") (pinfunction "G_1") (pintype "passive"))
      (node (ref "R25") (pin "1") (pinfunction "1_1") (pintype "passive"))
    )
    (net (code "33") (name "Net-(R2-Pad1)") (class "Default")
      (node (ref "R2") (pin "1") (pinfunction "1_1") (pintype "passive"))
      (node (ref "RESET") (pin "3") (pinfunction "2_3") (pintype "passive"))
      (node (ref "RESET") (pin "4") (pinfunction "2_4") (pintype "passive"))
    )
    (net (code "34") (name "Net-(U1-GPIO3)") (class "Default")
      (node (ref "U1") (pin "5") (pinfunction "GPIO3_5") (pintype "bidirectional"))
      (node (ref "USR_BUTTON") (pin "1") (pinfunction "1_1") (pintype "passive"))
      (node (ref "USR_BUTTON") (pin "2") (pinfunction "1_2") (pintype "passive"))
    )
    (net (code "35") (name "Net-(U1-USB_D+)") (class "Default")
      (node (ref "R3") (pin "2") (pinfunction "2_2") (pintype "passive"))
      (node (ref "U1") (pin "52") (pinfunction "USB_D+_52") (pintype "bidirectional"))
    )
    (net (code "36") (name "Net-(U1-USB_D-)") (class "Default")
      (node (ref "R4") (pin "2") (pinfunction "2_2") (pintype "passive"))
      (node (ref "U1") (pin "51") (pinfunction "USB_D-_51") (pintype "bidirectional"))
    )
    (net (code "37") (name "Net-(U1-VREG_AVDD)") (class "Default")
      (node (ref "C10") (pin "1") (pinfunction "1_1") (pintype "passive"))
      (node (ref "R1") (pin "2") (pinfunction "2_2") (pintype "passive"))
      (node (ref "U1") (pin "46") (pinfunction "VREG_AVDD_46") (pintype "bidirectional"))
    )
    (net (code "38") (name "Net-(U1-XIN)") (class "Default")
      (node (ref "C19") (pin "1") (pinfunction "1_1") (pintype "passive"))
      (node (ref "U1") (pin "21") (pinfunction "XIN_21") (pintype "bidirectional"))
      (node (ref "Y1") (pin "1") (pinfunction "1_1") (pintype "passive"))
    )
    (net (code "39") (name "Net-(U1-XOUT)") (class "Default")
      (node (ref "R8") (pin "2") (pinfunction "2_2") (pintype "passive"))
      (node (ref "U1") (pin "22") (pinfunction "XOUT_22") (pintype "bidirectional"))
    )
    (net (code "40") (name "Net-(U3-IO8)") (class "Default")
      (node (ref "R13") (pin "1") (pinfunction "1_1") (pintype "passive"))
      (node (ref "U3") (pin "22") (pinfunction "IO8_22") (pintype "bidirectional"))
    )
    (net (code "41") (name "Net-(U6-VSEL)") (class "Default")
      (node (ref "R19") (pin "1") (pinfunction "1_1") (pintype "passive"))
      (node (ref "R20") (pin "2") (pinfunction "2_2") (pintype "passive"))
      (node (ref "U6") (pin "P13") (pinfunction "VSEL_P13") (pintype "bidirectional"))
    )
    (net (code "42") (name "Net-(U8-A1)") (class "Default")
      (node (ref "R17") (pin "2") (pinfunction "2_2") (pintype "passive"))
      (node (ref "U8") (pin "1") (pinfunction "A1_1") (pintype "passive"))
    )
    (net (code "43") (name "Net-(U8-A2)") (class "Default")
      (node (ref "R16") (pin "2") (pinfunction "2_2") (pintype "passive"))
      (node (ref "U8") (pin "4") (pinfunction "A2_4") (pintype "passive"))
    )
    (net (code "44") (name "Net-(U9-ACG)") (class "Default")
      (node (ref "C31") (pin "1") (pinfunction "1_1") (pintype "passive"))
      (node (ref "U9") (pin "1") (pinfunction "ACG_1") (pintype "passive"))
    )
    (net (code "45") (name "Net-(U9-INP)") (class "Default")
      (node (ref "C33") (pin "1") (pinfunction "1_1") (pintype "passive"))
      (node (ref "L3") (pin "2") (pinfunction "2_2") (pintype "passive"))
      (node (ref "R18") (pin "2") (pinfunction "2_2") (pintype "passive"))
      (node (ref "U9") (pin "3") (pinfunction "INP_3") (pintype "bidirectional"))
    )
    (net (code "46") (name "Net-(U10-OSCI)") (class "Default")
      (node (ref "C47") (pin "2") (pinfunction "2_2") (pintype "passive"))
      (node (ref "U10") (pin "1") (pinfunction "OSCI_1") (pintype "input"))
      (node (ref "XTAL1") (pin "2") (pinfunction "2_2") (pintype "passive"))
    )
    (net (code "47") (name "Net-(U10-OSCO)") (class "Default")
      (node (ref "C48") (pin "2") (pinfunction "2_2") (pintype "passive"))
      (node (ref "U10") (pin "2") (pinfunction "OSCO_2") (pintype "output"))
      (node (ref "XTAL1") (pin "1") (pinfunction "1_1") (pintype "passive"))
    )
    (net (code "48") (name "Net-(U11-DO)") (class "Default")
      (node (ref "U11") (pin "P$2") (pinfunction "DO_P$2") (pintype "bidirectional"))
      (node (ref "U12") (pin "P$4") (pinfunction "DI_P$4") (pintype "bidirectional"))
    )
    (net (code "49") (name "Net-(U12-DO)") (class "Default")
      (node (ref "U12") (pin "P$2") (pinfunction "DO_P$2") (pintype "bidirectional"))
      (node (ref "U13") (pin "P$4") (pinfunction "DI_P$4") (pintype "bidirectional"))
    )
    (net (code "50") (name "Net-(U13-DO)") (class "Default")
      (node (ref "U13") (pin "P$2") (pinfunction "DO_P$2") (pintype "bidirectional"))
      (node (ref "U14") (pin "P$4") (pinfunction "DI_P$4") (pintype "bidirectional"))
    )
    (net (code "51") (name "Net-(Y1-2)") (class "Default")
      (node (ref "C18") (pin "1") (pinfunction "1_1") (pintype "passive"))
      (node (ref "R8") (pin "1") (pinfunction "1_1") (pintype "passive"))
      (node (ref "Y1") (pin "3") (pinfunction "2_3") (pintype "passive"))
    )
    (net (code "52") (name "PDIS") (class "Default")
      (node (ref "Q1") (pin "3") (pinfunction "D_3") (pintype "passive"))
      (node (ref "R23") (pin "1") (pinfunction "1_1") (pintype "passive"))
      (node (ref "U6") (pin "P8") (pinfunction "PDIS_P8") (pintype "bidirectional"))
    )
    (net (code "53") (name "PDIS_EN") (class "Default")
      (node (ref "Q1") (pin "1") (pinfunction "G_1") (pintype "passive"))
      (node (ref "R24") (pin "1") (pinfunction "1_1") (pintype "passive"))
      (node (ref "U1") (pin "12") (pinfunction "GPIO8_12") (pintype "bidirectional"))
    )
    (net (code "54") (name "PRB1") (class "Default")
      (node (ref "J4") (pin "1") (pinfunction "1_1") (pintype "passive"))
      (node (ref "U$2") (pin "P$4") (pinfunction "PRB_P$4") (pintype "bidirectional"))
    )
    (net (code "55") (name "PRB1_GND") (class "Default")
      (node (ref "J4") (pin "2") (pinfunction "2_2") (pintype "passive"))
      (node (ref "J4") (pin "3") (pinfunction "2_3") (pintype "passive"))
      (node (ref "U$2") (pin "P$5") (pinfunction "PRB_GND_P$5") (pintype "bidirectional"))
    )
    (net (code "56") (name "PROBE2") (class "Default")
      (node (ref "J5") (pin "1") (pinfunction "1_1") (pintype "passive"))
      (node (ref "U$3") (pin "P$4") (pinfunction "PRB_P$4") (pintype "bidirectional"))
    )
    (net (code "57") (name "PROBE2_GND") (class "Default")
      (node (ref "J5") (pin "2") (pinfunction "2_2") (pintype "passive"))
      (node (ref "J5") (pin "3") (pinfunction "2_3") (pintype "passive"))
      (node (ref "U$3") (pin "P$5") (pinfunction "PRB_GND_P$5") (pintype "bidirectional"))
    )
    (net (code "58") (name "QSPI_CLK") (class "Default")
      (node (ref "IC1") (pin "6") (pinfunction "CLK_6") (pintype "bidirectional"))
      (node (ref "U1") (pin "56") (pinfunction "QSPI_SCLK_56") (pintype "bidirectional"))
      (node (ref "U2") (pin "6") (pinfunction "SCLK_6") (pintype "bidirectional"))
    )
    (net (code "59") (name "SCL") (class "Default")
      (node (ref "J3") (pin "4") (pinfunction "4_4") (pintype "passive"))
      (node (ref "R12") (pin "1") (pinfunction "1_1") (pintype "passive"))
      (node (ref "U1") (pin "37") (pinfunction "GPIO25_37") (pintype "bidirectional"))
      (node (ref "U10") (pin "6") (pinfunction "SCL_6") (pintype "input"))
      (node (ref "U5") (pin "4") (pinfunction "SCK_4") (pintype "input"))
      (node (ref "U6") (pin "P2") (pinfunction "SCL2_P2") (pintype "bidirectional"))
      (node (ref "U7") (pin "2") (pinfunction "SCL_2") (pintype "input"))
      (node (ref "U9") (pin "11") (pinfunction "I2CL/SCL_11") (pintype "input"))
    )
    (net (code "60") (name "SCL_ISO") (class "Default")
      (node (ref "R22") (pin "1") (pinfunction "1_1") (pintype "passive"))
      (node (ref "U$2") (pin "P$8") (pinfunction "SCL_P$8") (pintype "bidirectional"))
      (node (ref "U$3") (pin "P$8") (pinfunction "SCL_P$8") (pintype "bidirectional"))
      (node (ref "U6") (pin "P19") (pinfunction "SCL1_P19") (pintype "bidirectional"))
    )
    (net (code "61") (name "SDA") (class "Default")
      (node (ref "J3") (pin "3") (pinfunction "3_3") (pintype "passive"))
      (node (ref "R11") (pin "1") (pinfunction "1_1") (pintype "passive"))
      (node (ref "U1") (pin "36") (pinfunction "GPIO24_36") (pintype "bidirectional"))
      (node (ref "U10") (pin "5") (pinfunction "SDA_5") (pintype "bidirectional"))
      (node (ref "U5") (pin "3") (pinfunction "SDI_3") (pintype "bidirectional"))
      (node (ref "U6") (pin "P3") (pinfunction "SDA2_P3") (pintype "bidirectional"))
      (node (ref "U7") (pin "3") (pinfunction "SDA_3") (pintype "bidirectional"))
      (node (ref "U9") (pin "13") (pinfunction "I2CD/MOSI_13") (pintype "bidirectional"))
    )
    (net (code "62") (name "SDA_ISO") (class "Default")
      (node (ref "R21") (pin "1") (pinfunction "1_1") (pintype "passive"))
      (node (ref "U$2") (pin "P$1") (pinfunction "SDA_P$1") (pintype "bidirectional"))
      (node (ref "U$3") (pin "P$1") (pinfunction "SDA_P$1") (pintype "bidirectional"))
      (node (ref "U6") (pin "P18") (pinfunction "SDA1_P18") (pintype "bidirectional"))
    )
    (net (code "63") (name "SD_CLK") (class "Default")
      (node (ref "U$1") (pin "P5") (pinfunction "CLK_P5") (pintype "bidirectional"))
      (node (ref "U1") (pin "18") (pinfunction "GPIO14_18") (pintype "bidirectional"))
    )
    (net (code "64") (name "SIO0") (class "Default")
      (node (ref "IC1") (pin "5") (pinfunction "DI(IO0)_5") (pintype "bidirectional"))
      (node (ref "U1") (pin "57") (pinfunction "QSPI_SD0_57") (pintype "bidirectional"))
      (node (ref "U2") (pin "5") (pinfunction "SI/SIO0_5") (pintype "bidirectional"))
    )
    (net (code "65") (name "SIO1") (class "Default")
      (node (ref "IC1") (pin "2") (pinfunction "DO(IO1)_2") (pintype "bidirectional"))
      (node (ref "U1") (pin "59") (pinfunction "QSPI_SD1_59") (pintype "bidirectional"))
      (node (ref "U2") (pin "2") (pinfunction "SO/SIO1_2") (pintype "bidirectional"))
    )
    (net (code "66") (name "SIO2") (class "Default")
      (node (ref "IC1") (pin "3") (pinfunction "~{WP(IO2})_3") (pintype "bidirectional"))
      (node (ref "U1") (pin "58") (pinfunction "QSPI_SD2_58") (pintype "bidirectional"))
      (node (ref "U2") (pin "3") (pinfunction "SIO2_3") (pintype "bidirectional"))
    )
    (net (code "67") (name "SIO3") (class "Default")
      (node (ref "IC1") (pin "7") (pinfunction "~{HOLD_OR_}RESET_(IO3)_7") (pintype "bidirectional"))
      (node (ref "U1") (pin "55") (pinfunction "QSPI_SD3_55") (pintype "bidirectional"))
      (node (ref "U2") (pin "7") (pinfunction "SIO3_7") (pintype "bidirectional"))
    )
    (net (code "68") (name "SWCLK") (class "Default")
      (node (ref "J1") (pin "1") (pinfunction "1_1") (pintype "passive"))
      (node (ref "U1") (pin "24") (pinfunction "SWCLK_24") (pintype "bidirectional"))
    )
    (net (code "69") (name "SWDIO") (class "Default")
      (node (ref "J1") (pin "3") (pinfunction "3_3") (pintype "passive"))
      (node (ref "U1") (pin "25") (pinfunction "SWDIO_25") (pintype "bidirectional"))
    )
    (net (code "70") (name "SWITCH") (class "Default")
      (node (ref "U$1") (pin "G1") (pinfunction "SWITCH_G1") (pintype "bidirectional"))
      (node (ref "U1") (pin "13") (pinfunction "GPIO9_13") (pintype "bidirectional"))
    )
    (net (code "71") (name "USB_N") (class "Default")
      (node (ref "J2") (pin "A7") (pinfunction "DN1_A7") (pintype "bidirectional"))
      (node (ref "J2") (pin "B7") (pinfunction "DN2_B7") (pintype "bidirectional"))
      (node (ref "R4") (pin "1") (pinfunction "1_1") (pintype "passive"))
    )
    (net (code "72") (name "USB_P") (class "Default")
      (node (ref "J2") (pin "A6") (pinfunction "DP1_A6") (pintype "bidirectional"))
      (node (ref "J2") (pin "B6") (pinfunction "DP2_B6") (pintype "bidirectional"))
      (node (ref "R3") (pin "1") (pinfunction "1_1") (pintype "passive"))
    )
    (net (code "73") (name "VCC-ISO") (class "Default")
      (node (ref "C37") (pin "1") (pinfunction "1_1") (pintype "passive"))
      (node (ref "C38") (pin "1") (pinfunction "1_1") (pintype "passive"))
      (node (ref "C39") (pin "1") (pinfunction "1_1") (pintype "passive"))
      (node (ref "C40") (pin "2") (pinfunction "2_2") (pintype "passive"))
      (node (ref "C41") (pin "2") (pinfunction "2_2") (pintype "passive"))
      (node (ref "R19") (pin "2") (pinfunction "2_2") (pintype "passive"))
      (node (ref "R21") (pin "2") (pinfunction "2_2") (pintype "passive"))
      (node (ref "R22") (pin "2") (pinfunction "2_2") (pintype "passive"))
      (node (ref "U$2") (pin "P$3") (pinfunction "VCC_P$3") (pintype "power_in"))
      (node (ref "U$3") (pin "P$3") (pinfunction "VCC_P$3") (pintype "power_in"))
      (node (ref "U6") (pin "P12") (pinfunction "VISO_P12") (pintype "bidirectional"))
      (node (ref "U6") (pin "P17") (pinfunction "VDDISO_P17") (pintype "bidirectional"))
    )
    (net (code "74") (name "V_USB") (class "Default")
      (node (ref "C22") (pin "1") (pinfunction "1_1") (pintype "passive"))
      (node (ref "C23") (pin "2") (pinfunction "2_2") (pintype "passive"))
      (node (ref "C34") (pin "2") (pinfunction "2_2") (pintype "passive"))
      (node (ref "C35") (pin "2") (pinfunction "2_2") (pintype "passive"))
      (node (ref "C45") (pin "1") (pinfunction "1_1") (pintype "passive"))
      (node (ref "C49") (pin "1") (pinfunction "1_1") (pintype "passive"))
      (node (ref "C50") (pin "1") (pinfunction "1_1") (pintype "passive"))
      (node (ref "C51") (pin "1") (pinfunction "1_1") (pintype "passive"))
      (node (ref "C52") (pin "1") (pinfunction "1_1") (pintype "passive"))
      (node (ref "L2") (pin "2") (pinfunction "2_2") (pintype "passive"))
      (node (ref "R23") (pin "2") (pinfunction "2_2") (pintype "passive"))
      (node (ref "U11") (pin "P$1") (pinfunction "VCC_P$1") (pintype "bidirectional"))
      (node (ref "U12") (pin "P$1") (pinfunction "VCC_P$1") (pintype "bidirectional"))
      (node (ref "U13") (pin "P$1") (pinfunction "VCC_P$1") (pintype "bidirectional"))
      (node (ref "U14") (pin "P$1") (pinfunction "VCC_P$1") (pintype "bidirectional"))
      (node (ref "U15") (pin "6") (pinfunction "VCCB_6") (pintype "power_in"))
      (node (ref "U4") (pin "1") (pinfunction "VIN_1") (pintype "input"))
      (node (ref "U4") (pin "3") (pinfunction "EN_3") (pintype "input"))
      (node (ref "U6") (pin "P9") (pinfunction "VIN_P9") (pintype "bidirectional"))
      (node (ref "USB") (pin "TP") (pinfunction "TP_TP") (pintype "input"))
    )
    (net (code "75") (name "unconnected-(J2-SBU1-PadA8)") (class "Default")
      (node (ref "J2") (pin "A8") (pinfunction "SBU1_A8") (pintype "bidirectional"))
    )
    (net (code "76") (name "unconnected-(J2-SBU2-PadB8)") (class "Default")
      (node (ref "J2") (pin "B8") (pinfunction "SBU2_B8") (pintype "bidirectional"))
    )
    (net (code "77") (name "unconnected-(J6-Pad01)") (class "Default")
      (node (ref "J6") (pin "01") (pinfunction "01_01") (pintype "passive"))
    )
    (net (code "78") (name "unconnected-(J6-Pad02)") (class "Default")
      (node (ref "J6") (pin "02") (pinfunction "02_02") (pintype "passive"))
    )
    (net (code "79") (name "unconnected-(U$2-NC-PadP$2)") (class "Default")
      (node (ref "U$2") (pin "P$2") (pinfunction "NC_P$2") (pintype "no_connect"))
    )
    (net (code "80") (name "unconnected-(U$2-NC-PadP$9)") (class "Default")
      (node (ref "U$2") (pin "P$9") (pinfunction "NC_P$9") (pintype "no_connect"))
    )
    (net (code "81") (name "unconnected-(U$2-NC-PadP$10)") (class "Default")
      (node (ref "U$2") (pin "P$10") (pinfunction "NC_P$10") (pintype "no_connect"))
    )
    (net (code "82") (name "unconnected-(U$3-NC-PadP$2)") (class "Default")
      (node (ref "U$3") (pin "P$2") (pinfunction "NC_P$2") (pintype "no_connect"))
    )
    (net (code "83") (name "unconnected-(U$3-NC-PadP$9)") (class "Default")
      (node (ref "U$3") (pin "P$9") (pinfunction "NC_P$9") (pintype "no_connect"))
    )
    (net (code "84") (name "unconnected-(U$3-NC-PadP$10)") (class "Default")
      (node (ref "U$3") (pin "P$10") (pinfunction "NC_P$10") (pintype "no_connect"))
    )
    (net (code "85") (name "unconnected-(U1-GPIO27{slash}ADC1-Pad41)") (class "Default")
      (node (ref "U1") (pin "41") (pinfunction "GPIO27/ADC1_41") (pintype "bidirectional"))
    )
    (net (code "86") (name "unconnected-(U1-GPIO28{slash}ADC2-Pad42)") (class "Default")
      (node (ref "U1") (pin "42") (pinfunction "GPIO28/ADC2_42") (pintype "bidirectional"))
    )
    (net (code "87") (name "unconnected-(U1-GPIO29{slash}ADC3-Pad43)") (class "Default")
      (node (ref "U1") (pin "43") (pinfunction "GPIO29/ADC3_43") (pintype "bidirectional"))
    )
    (net (code "88") (name "unconnected-(U3-IO0-Pad12)") (class "Default")
      (node (ref "U3") (pin "12") (pinfunction "IO0_12") (pintype "bidirectional"))
    )
    (net (code "89") (name "unconnected-(U3-IO1-Pad13)") (class "Default")
      (node (ref "U3") (pin "13") (pinfunction "IO1_13") (pintype "bidirectional"))
    )
    (net (code "90") (name "unconnected-(U3-IO4-Pad18)") (class "Default")
      (node (ref "U3") (pin "18") (pinfunction "IO4_18") (pintype "bidirectional"))
    )
    (net (code "91") (name "unconnected-(U3-IO5-Pad19)") (class "Default")
      (node (ref "U3") (pin "19") (pinfunction "IO5_19") (pintype "bidirectional"))
    )
    (net (code "92") (name "unconnected-(U3-IO18-Pad26)") (class "Default")
      (node (ref "U3") (pin "26") (pinfunction "IO18_26") (pintype "bidirectional"))
    )
    (net (code "93") (name "unconnected-(U3-IO19-Pad27)") (class "Default")
      (node (ref "U3") (pin "27") (pinfunction "IO19_27") (pintype "bidirectional"))
    )
    (net (code "94") (name "unconnected-(U3-NC-Pad4)") (class "Default")
      (node (ref "U3") (pin "4") (pinfunction "NC_4") (pintype "no_connect"))
    )
    (net (code "95") (name "unconnected-(U3-NC-Pad7)") (class "Default")
      (node (ref "U3") (pin "7") (pinfunction "NC_7") (pintype "no_connect"))
    )
    (net (code "96") (name "unconnected-(U3-NC-Pad9)") (class "Default")
      (node (ref "U3") (pin "9") (pinfunction "NC_9") (pintype "no_connect"))
    )
    (net (code "97") (name "unconnected-(U3-NC-Pad10)") (class "Default")
      (node (ref "U3") (pin "10") (pinfunction "NC_10") (pintype "no_connect"))
    )
    (net (code "98") (name "unconnected-(U3-NC-Pad15)") (class "Default")
      (node (ref "U3") (pin "15") (pinfunction "NC_15") (pintype "no_connect"))
    )
    (net (code "99") (name "unconnected-(U3-NC-Pad17)") (class "Default")
      (node (ref "U3") (pin "17") (pinfunction "NC_17") (pintype "no_connect"))
    )
    (net (code "100") (name "unconnected-(U3-NC-Pad24)") (class "Default")
      (node (ref "U3") (pin "24") (pinfunction "NC_24") (pintype "no_connect"))
    )
    (net (code "101") (name "unconnected-(U3-NC-Pad25)") (class "Default")
      (node (ref "U3") (pin "25") (pinfunction "NC_25") (pintype "no_connect"))
    )
    (net (code "102") (name "unconnected-(U3-NC-Pad28)") (class "Default")
      (node (ref "U3") (pin "28") (pinfunction "NC_28") (pintype "no_connect"))
    )
    (net (code "103") (name "unconnected-(U3-NC-Pad29)") (class "Default")
      (node (ref "U3") (pin "29") (pinfunction "NC_29") (pintype "no_connect"))
    )
    (net (code "104") (name "unconnected-(U3-NC-Pad32)") (class "Default")
      (node (ref "U3") (pin "32") (pinfunction "NC_32") (pintype "no_connect"))
    )
    (net (code "105") (name "unconnected-(U3-NC-Pad33)") (class "Default")
      (node (ref "U3") (pin "33") (pinfunction "NC_33") (pintype "no_connect"))
    )
    (net (code "106") (name "unconnected-(U3-NC-Pad34)") (class "Default")
      (node (ref "U3") (pin "34") (pinfunction "NC_34") (pintype "no_connect"))
    )
    (net (code "107") (name "unconnected-(U3-NC-Pad35)") (class "Default")
      (node (ref "U3") (pin "35") (pinfunction "NC_35") (pintype "no_connect"))
    )
    (net (code "108") (name "unconnected-(U9-NC-Pad14)") (class "Default")
      (node (ref "U9") (pin "14") (pinfunction "NC_14") (pintype "no_connect"))
    )
    (net (code "109") (name "unconnected-(U10-CLKOUT-Pad7)") (class "Default")
      (node (ref "U10") (pin "7") (pinfunction "CLKOUT_7") (pintype "output"))
    )
    (net (code "110") (name "unconnected-(U14-DO-PadP$2)") (class "Default")
      (node (ref "U14") (pin "P$2") (pinfunction "DO_P$2") (pintype "bidirectional"))
    )
    (net (code "111") (name "~{ESP32_BOOT}") (class "Default")
      (node (ref "U1") (pin "31") (pinfunction "GPIO19_31") (pintype "bidirectional"))
      (node (ref "U3") (pin "23") (pinfunction "IO9_23") (pintype "bidirectional"))
    )
    (net (code "112") (name "~{ESP32_RST}") (class "Default")
      (node (ref "U1") (pin "29") (pinfunction "GPIO18_29") (pintype "bidirectional"))
      (node (ref "U3") (pin "8") (pinfunction "EN_8") (pintype "input"))
    )
    (net (code "113") (name "~{FLASH_CS}") (class "Default")
      (node (ref "R7") (pin "2") (pinfunction "2_2") (pintype "passive"))
      (node (ref "U1") (pin "2") (pinfunction "GPIO0_2") (pintype "bidirectional"))
      (node (ref "U2") (pin "1") (pinfunction "~{CE}_1") (pintype "bidirectional"))
    )
    (net (code "114") (name "~{QSPI_CS}") (class "Default")
      (node (ref "IC1") (pin "1") (pinfunction "~{CS}_1") (pintype "bidirectional"))
      (node (ref "R5") (pin "1") (pinfunction "1_1") (pintype "passive"))
      (node (ref "R6") (pin "2") (pinfunction "2_2") (pintype "passive"))
      (node (ref "U1") (pin "60") (pinfunction "QSPI_~{CS}_60") (pintype "bidirectional"))
    )
    (net (code "115") (name "~{RESET}") (class "Default")
      (node (ref "RESET") (pin "1") (pinfunction "1_1") (pintype "passive"))
      (node (ref "RESET") (pin "2") (pinfunction "1_2") (pintype "passive"))
      (node (ref "U1") (pin "26") (pinfunction "RUN_26") (pintype "bidirectional"))
    )
    (net (code "116") (name "~{USB_BOOT}") (class "Default")
      (node (ref "!BOOT") (pin "3") (pinfunction "2_3") (pintype "passive"))
      (node (ref "!BOOT") (pin "4") (pinfunction "2_4") (pintype "passive"))
      (node (ref "R6") (pin "1") (pinfunction "1_1") (pintype "passive"))
    )
  )
)
